# Adapter.net
KiCad netlist of a schematic drawn in EAGLE
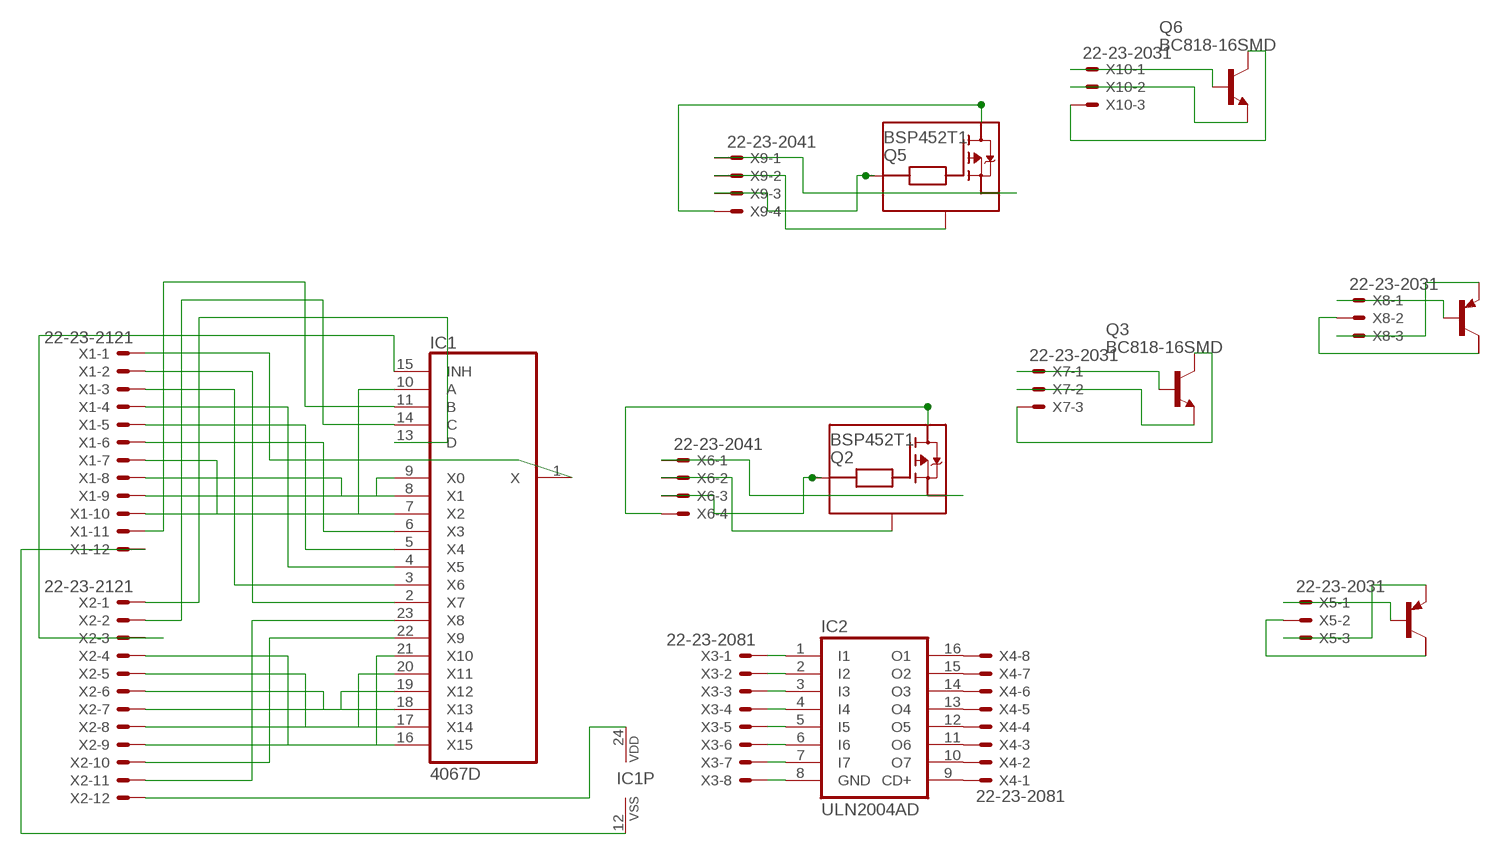
[diagram p0: schematic, sheet 1]
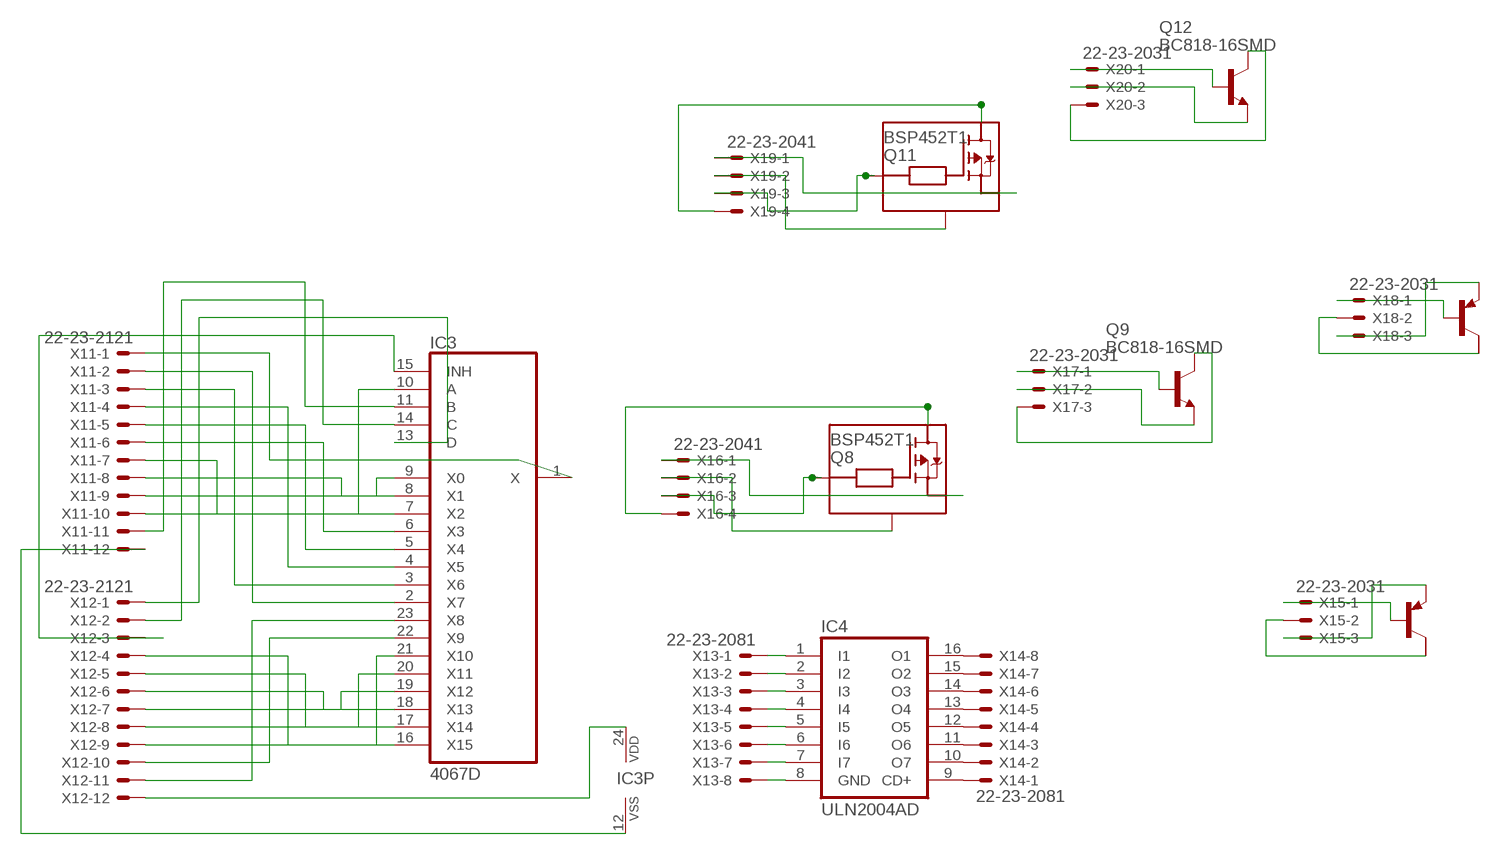
[diagram p1: schematic, sheet 2]
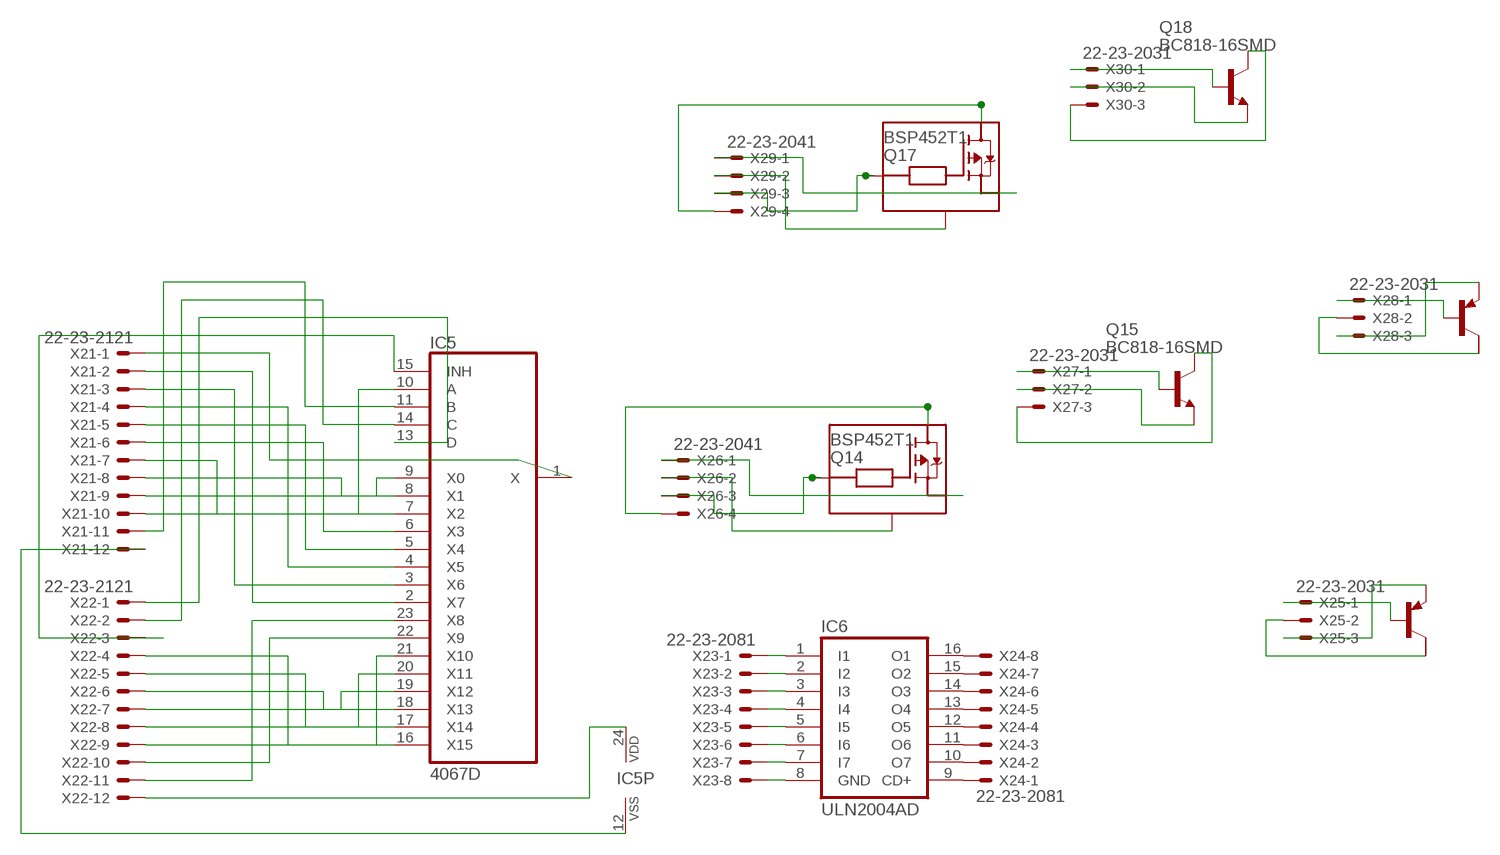
[diagram p2: schematic, sheet 3]
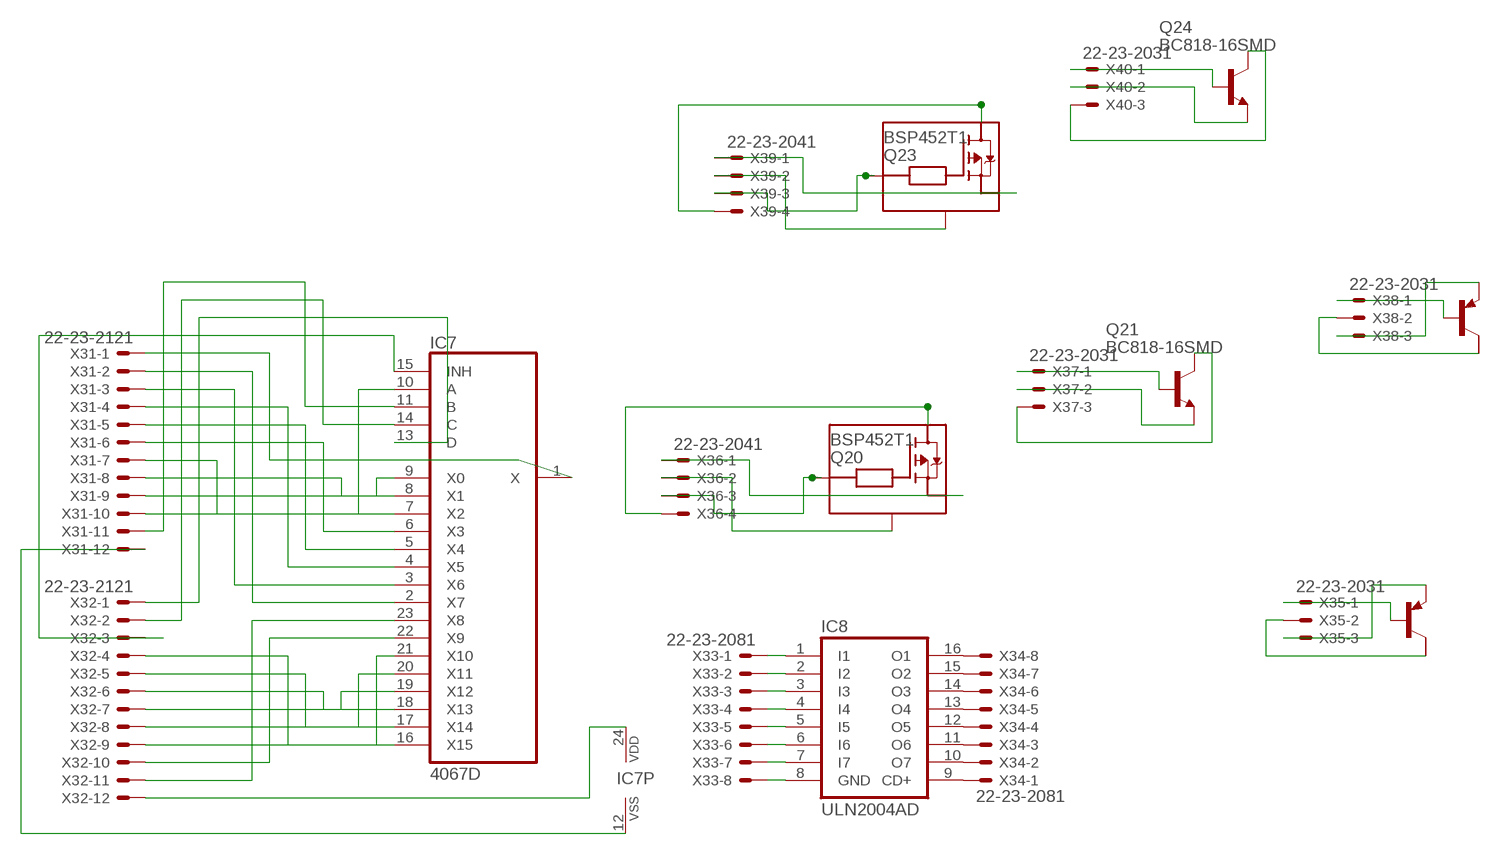
[diagram p3: schematic, sheet 4]
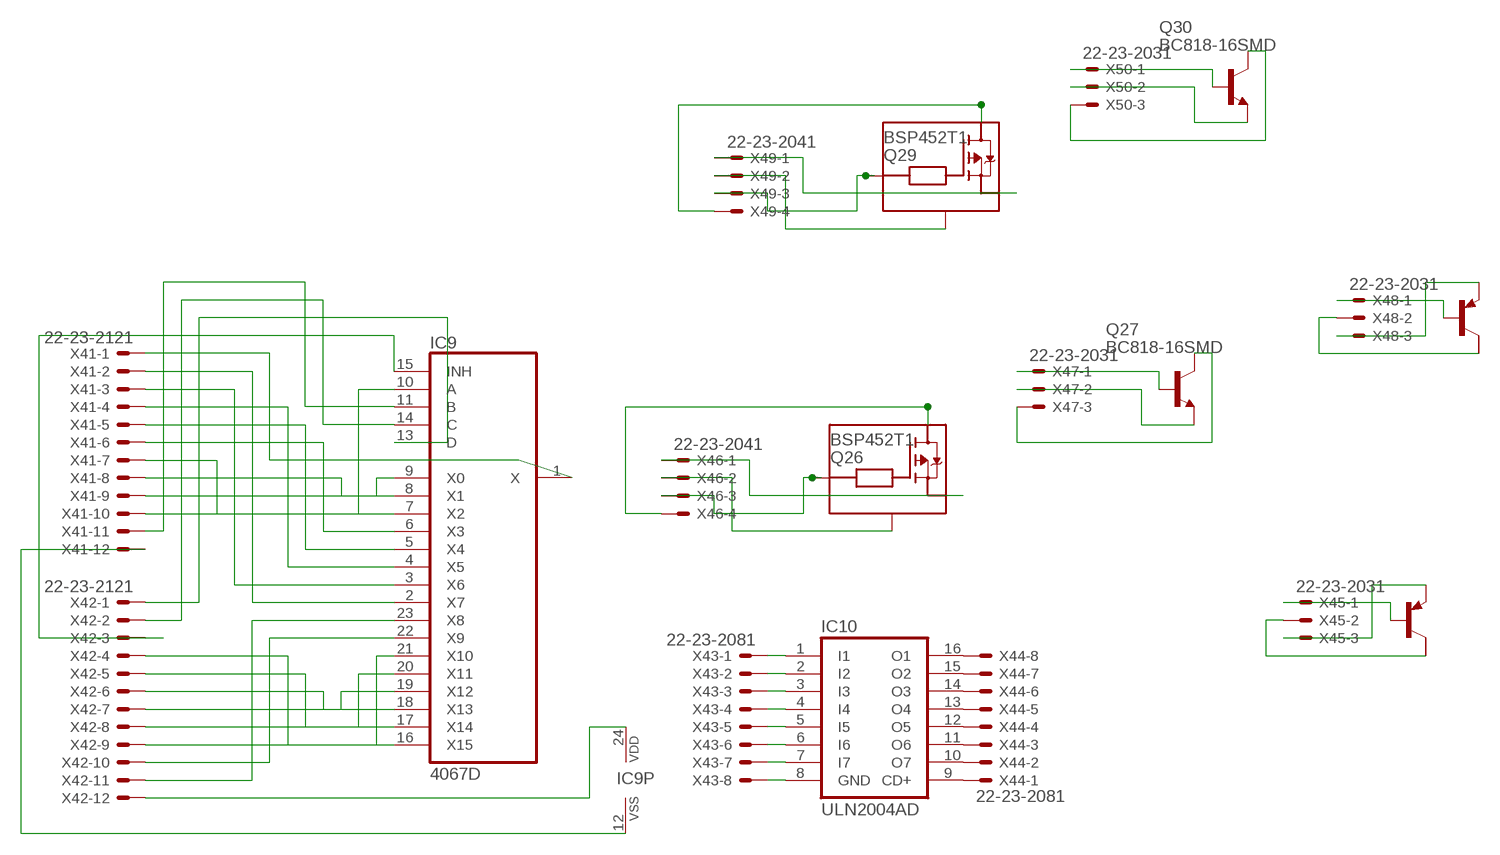
[diagram p4: schematic, sheet 5]
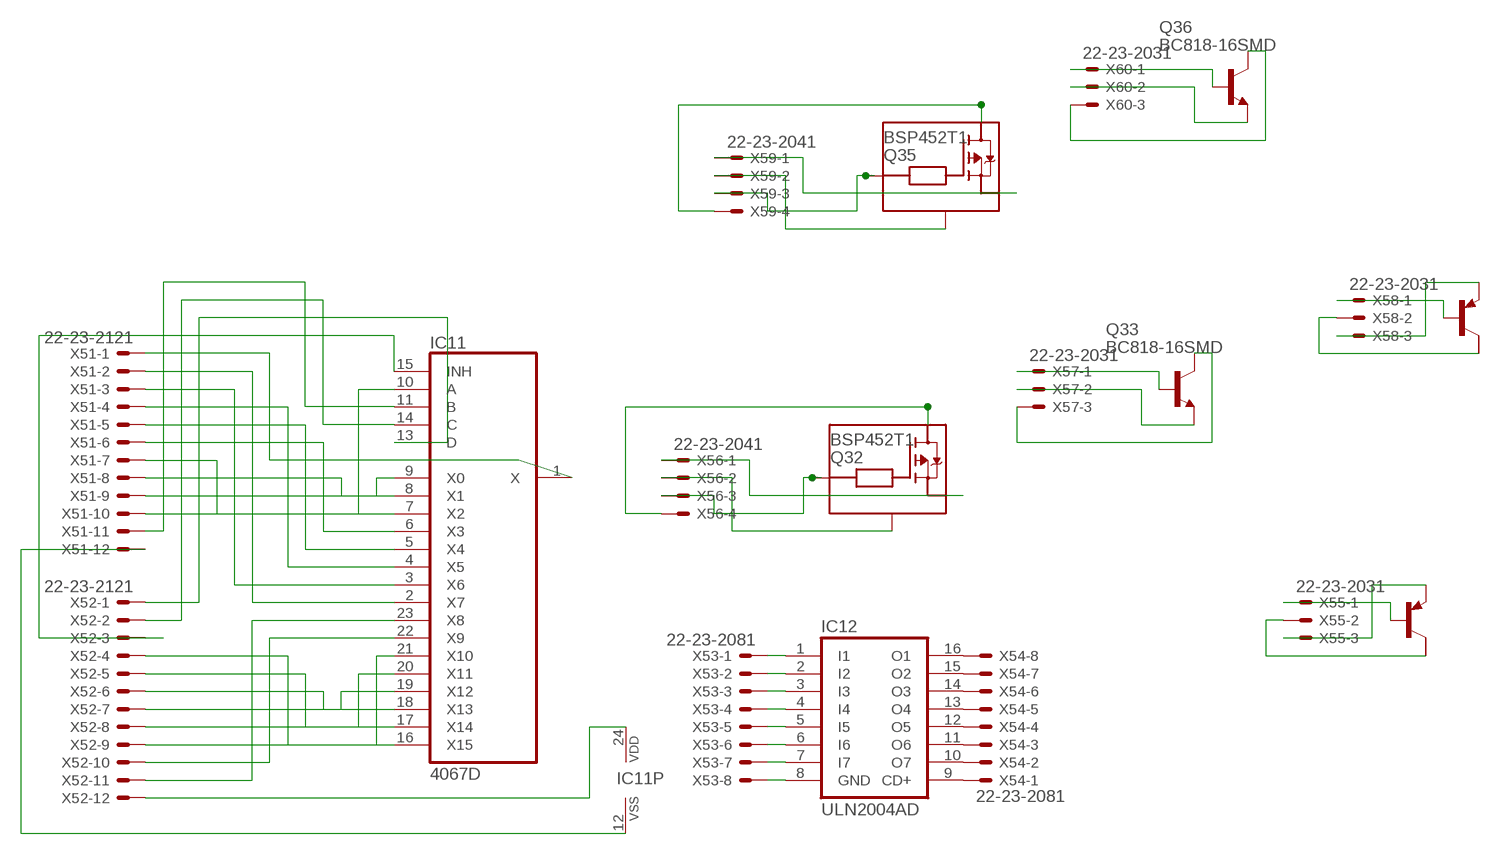
[diagram p5: schematic, sheet 6]
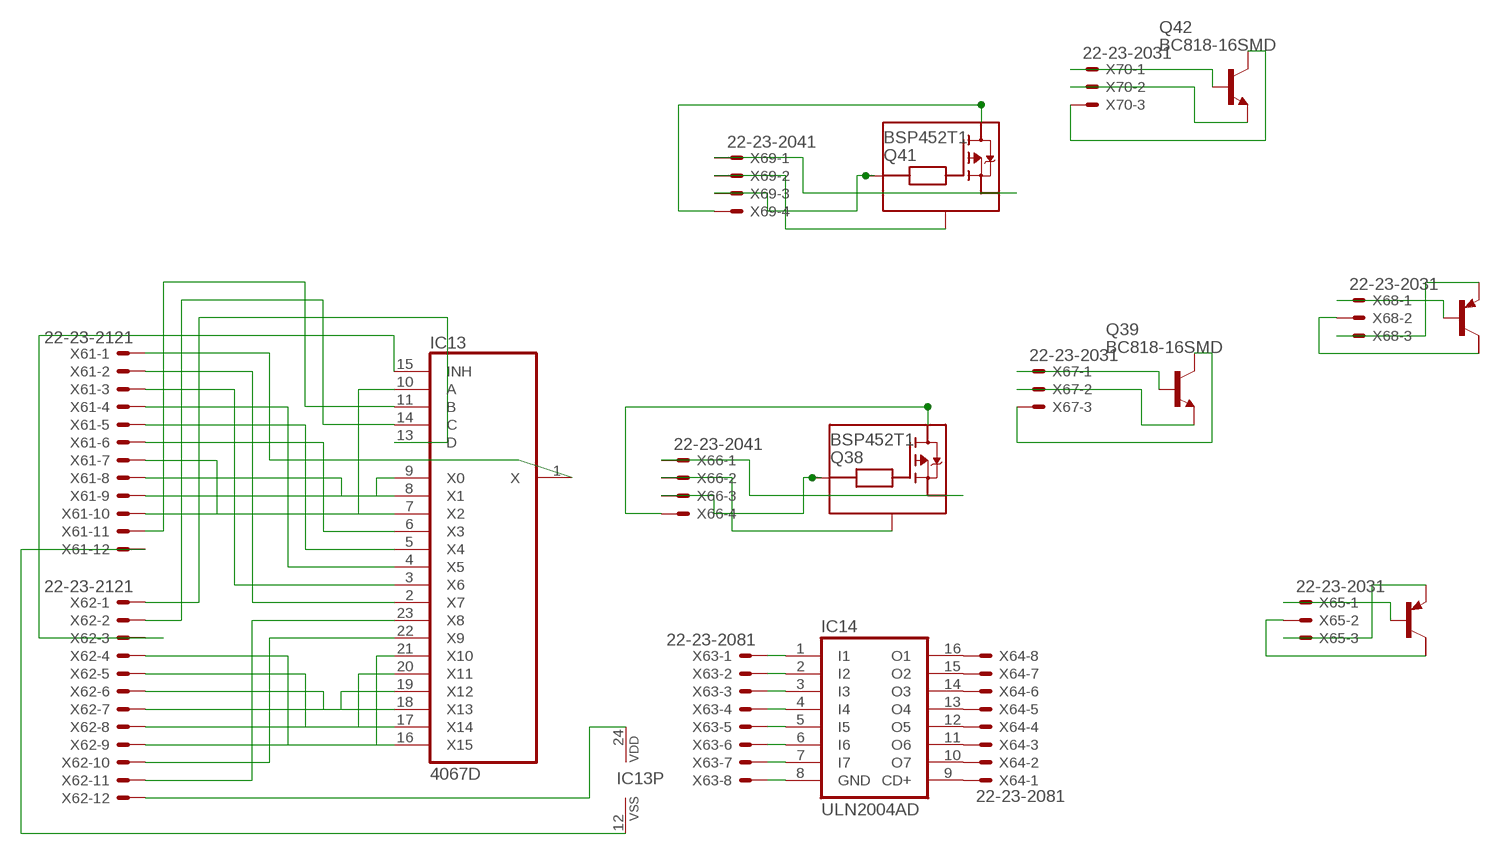
[diagram p6: schematic, sheet 7]
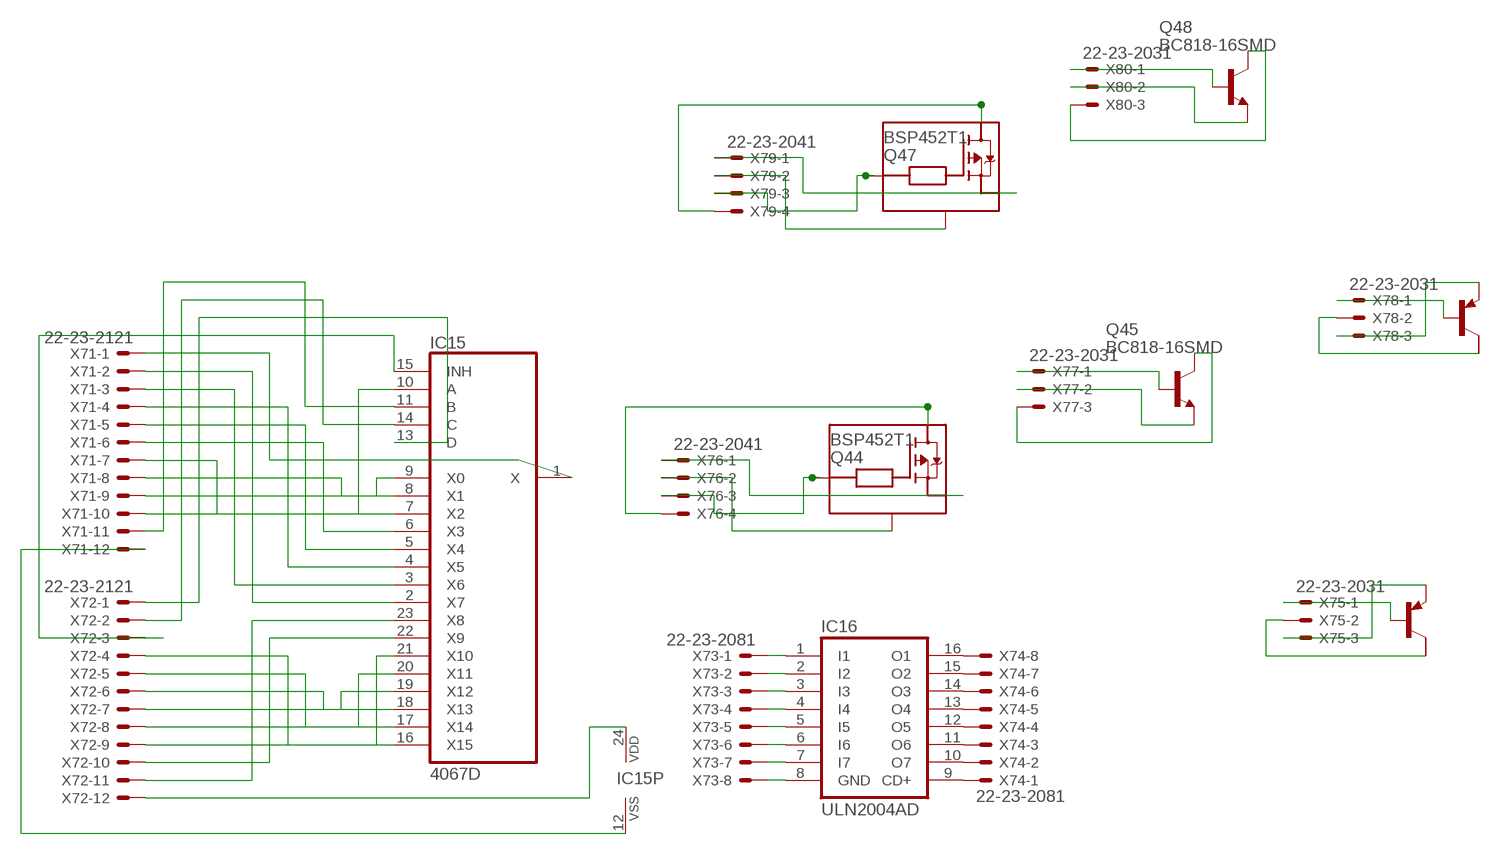
[diagram p7: schematic, sheet 8]

(export (version "E")
  (design (tool "Eeschema 10.0.6"))
  (components
    (comp (ref "IC11")
      (value "4067D")
      (footprint "eagle-import:SO24W")
      (libsource (lib "eagle-import") (part "4067D"))
    )
    (comp (ref "IC12")
      (value "ULN2004AD")
      (footprint "eagle-import:SO16")
      (libsource (lib "eagle-import") (part "ULN2004AD"))
    )
    (comp (ref "Q31")
      (value "BCP53T1")
      (footprint "eagle-import:SOT223")
      (libsource (lib "eagle-import") (part "BCP53T1"))
    )
    (comp (ref "Q32")
      (value "BSP452T1")
      (footprint "eagle-import:SOT223")
      (libsource (lib "eagle-import") (part "BSP452T1"))
    )
    (comp (ref "Q33")
      (value "BC818-16SMD")
      (footprint "eagle-import:SOT23-BEC")
      (libsource (lib "eagle-import") (part "BC818SMD-16"))
    )
    (comp (ref "Q34")
      (value "BCP53T1")
      (footprint "eagle-import:SOT223")
      (libsource (lib "eagle-import") (part "BCP53T1"))
    )
    (comp (ref "Q35")
      (value "BSP452T1")
      (footprint "eagle-import:SOT223")
      (libsource (lib "eagle-import") (part "BSP452T1"))
    )
    (comp (ref "Q36")
      (value "BC818-16SMD")
      (footprint "eagle-import:SOT23-BEC")
      (libsource (lib "eagle-import") (part "BC818SMD-16"))
    )
    (comp (ref "X51")
      (value "22-23-2121")
      (footprint "eagle-import:22-23-2121")
      (fields (field (name "MF") "MOLEX"))
      (libsource (lib "eagle-import") (part "22-23-2121"))
    )
    (comp (ref "X52")
      (value "22-23-2121")
      (footprint "eagle-import:22-23-2121")
      (fields (field (name "MF") "MOLEX"))
      (libsource (lib "eagle-import") (part "22-23-2121"))
    )
    (comp (ref "X53")
      (value "22-23-2081")
      (footprint "eagle-import:22-23-2081")
      (fields (field (name "MF") "MOLEX"))
      (libsource (lib "eagle-import") (part "22-23-2081"))
    )
    (comp (ref "X54")
      (value "22-23-2081")
      (footprint "eagle-import:22-23-2081")
      (fields (field (name "MF") "MOLEX"))
      (libsource (lib "eagle-import") (part "22-23-2081"))
    )
    (comp (ref "X55")
      (value "22-23-2031")
      (footprint "eagle-import:22-23-2031")
      (fields (field (name "MF") "MOLEX"))
      (libsource (lib "eagle-import") (part "22-23-2031"))
    )
    (comp (ref "X56")
      (value "22-23-2041")
      (footprint "eagle-import:22-23-2041")
      (fields (field (name "MF") "MOLEX"))
      (libsource (lib "eagle-import") (part "22-23-2041"))
    )
    (comp (ref "X57")
      (value "22-23-2031")
      (footprint "eagle-import:22-23-2031")
      (fields (field (name "MF") "MOLEX"))
      (libsource (lib "eagle-import") (part "22-23-2031"))
    )
    (comp (ref "X58")
      (value "22-23-2031")
      (footprint "eagle-import:22-23-2031")
      (fields (field (name "MF") "MOLEX"))
      (libsource (lib "eagle-import") (part "22-23-2031"))
    )
    (comp (ref "X59")
      (value "22-23-2041")
      (footprint "eagle-import:22-23-2041")
      (fields (field (name "MF") "MOLEX"))
      (libsource (lib "eagle-import") (part "22-23-2041"))
    )
    (comp (ref "X60")
      (value "22-23-2031")
      (footprint "eagle-import:22-23-2031")
      (fields (field (name "MF") "MOLEX"))
      (libsource (lib "eagle-import") (part "22-23-2031"))
    )
    (comp (ref "IC3")
      (value "4067D")
      (footprint "eagle-import:SO24W")
      (libsource (lib "eagle-import") (part "4067D"))
    )
    (comp (ref "IC4")
      (value "ULN2004AD")
      (footprint "eagle-import:SO16")
      (libsource (lib "eagle-import") (part "ULN2004AD"))
    )
    (comp (ref "Q7")
      (value "BCP53T1")
      (footprint "eagle-import:SOT223")
      (libsource (lib "eagle-import") (part "BCP53T1"))
    )
    (comp (ref "Q8")
      (value "BSP452T1")
      (footprint "eagle-import:SOT223")
      (libsource (lib "eagle-import") (part "BSP452T1"))
    )
    (comp (ref "Q9")
      (value "BC818-16SMD")
      (footprint "eagle-import:SOT23-BEC")
      (libsource (lib "eagle-import") (part "BC818SMD-16"))
    )
    (comp (ref "Q10")
      (value "BCP53T1")
      (footprint "eagle-import:SOT223")
      (libsource (lib "eagle-import") (part "BCP53T1"))
    )
    (comp (ref "Q11")
      (value "BSP452T1")
      (footprint "eagle-import:SOT223")
      (libsource (lib "eagle-import") (part "BSP452T1"))
    )
    (comp (ref "Q12")
      (value "BC818-16SMD")
      (footprint "eagle-import:SOT23-BEC")
      (libsource (lib "eagle-import") (part "BC818SMD-16"))
    )
    (comp (ref "X11")
      (value "22-23-2121")
      (footprint "eagle-import:22-23-2121")
      (fields (field (name "MF") "MOLEX"))
      (libsource (lib "eagle-import") (part "22-23-2121"))
    )
    (comp (ref "X12")
      (value "22-23-2121")
      (footprint "eagle-import:22-23-2121")
      (fields (field (name "MF") "MOLEX"))
      (libsource (lib "eagle-import") (part "22-23-2121"))
    )
    (comp (ref "X13")
      (value "22-23-2081")
      (footprint "eagle-import:22-23-2081")
      (fields (field (name "MF") "MOLEX"))
      (libsource (lib "eagle-import") (part "22-23-2081"))
    )
    (comp (ref "X14")
      (value "22-23-2081")
      (footprint "eagle-import:22-23-2081")
      (fields (field (name "MF") "MOLEX"))
      (libsource (lib "eagle-import") (part "22-23-2081"))
    )
    (comp (ref "X15")
      (value "22-23-2031")
      (footprint "eagle-import:22-23-2031")
      (fields (field (name "MF") "MOLEX"))
      (libsource (lib "eagle-import") (part "22-23-2031"))
    )
    (comp (ref "X16")
      (value "22-23-2041")
      (footprint "eagle-import:22-23-2041")
      (fields (field (name "MF") "MOLEX"))
      (libsource (lib "eagle-import") (part "22-23-2041"))
    )
    (comp (ref "X17")
      (value "22-23-2031")
      (footprint "eagle-import:22-23-2031")
      (fields (field (name "MF") "MOLEX"))
      (libsource (lib "eagle-import") (part "22-23-2031"))
    )
    (comp (ref "X18")
      (value "22-23-2031")
      (footprint "eagle-import:22-23-2031")
      (fields (field (name "MF") "MOLEX"))
      (libsource (lib "eagle-import") (part "22-23-2031"))
    )
    (comp (ref "X19")
      (value "22-23-2041")
      (footprint "eagle-import:22-23-2041")
      (fields (field (name "MF") "MOLEX"))
      (libsource (lib "eagle-import") (part "22-23-2041"))
    )
    (comp (ref "X20")
      (value "22-23-2031")
      (footprint "eagle-import:22-23-2031")
      (fields (field (name "MF") "MOLEX"))
      (libsource (lib "eagle-import") (part "22-23-2031"))
    )
    (comp (ref "IC15")
      (value "4067D")
      (footprint "eagle-import:SO24W")
      (libsource (lib "eagle-import") (part "4067D"))
    )
    (comp (ref "IC16")
      (value "ULN2004AD")
      (footprint "eagle-import:SO16")
      (libsource (lib "eagle-import") (part "ULN2004AD"))
    )
    (comp (ref "Q43")
      (value "BCP53T1")
      (footprint "eagle-import:SOT223")
      (libsource (lib "eagle-import") (part "BCP53T1"))
    )
    (comp (ref "Q44")
      (value "BSP452T1")
      (footprint "eagle-import:SOT223")
      (libsource (lib "eagle-import") (part "BSP452T1"))
    )
    (comp (ref "Q45")
      (value "BC818-16SMD")
      (footprint "eagle-import:SOT23-BEC")
      (libsource (lib "eagle-import") (part "BC818SMD-16"))
    )
    (comp (ref "Q46")
      (value "BCP53T1")
      (footprint "eagle-import:SOT223")
      (libsource (lib "eagle-import") (part "BCP53T1"))
    )
    (comp (ref "Q47")
      (value "BSP452T1")
      (footprint "eagle-import:SOT223")
      (libsource (lib "eagle-import") (part "BSP452T1"))
    )
    (comp (ref "Q48")
      (value "BC818-16SMD")
      (footprint "eagle-import:SOT23-BEC")
      (libsource (lib "eagle-import") (part "BC818SMD-16"))
    )
    (comp (ref "X71")
      (value "22-23-2121")
      (footprint "eagle-import:22-23-2121")
      (fields (field (name "MF") "MOLEX"))
      (libsource (lib "eagle-import") (part "22-23-2121"))
    )
    (comp (ref "X72")
      (value "22-23-2121")
      (footprint "eagle-import:22-23-2121")
      (fields (field (name "MF") "MOLEX"))
      (libsource (lib "eagle-import") (part "22-23-2121"))
    )
    (comp (ref "X73")
      (value "22-23-2081")
      (footprint "eagle-import:22-23-2081")
      (fields (field (name "MF") "MOLEX"))
      (libsource (lib "eagle-import") (part "22-23-2081"))
    )
    (comp (ref "X74")
      (value "22-23-2081")
      (footprint "eagle-import:22-23-2081")
      (fields (field (name "MF") "MOLEX"))
      (libsource (lib "eagle-import") (part "22-23-2081"))
    )
    (comp (ref "X75")
      (value "22-23-2031")
      (footprint "eagle-import:22-23-2031")
      (fields (field (name "MF") "MOLEX"))
      (libsource (lib "eagle-import") (part "22-23-2031"))
    )
    (comp (ref "X76")
      (value "22-23-2041")
      (footprint "eagle-import:22-23-2041")
      (fields (field (name "MF") "MOLEX"))
      (libsource (lib "eagle-import") (part "22-23-2041"))
    )
    (comp (ref "X77")
      (value "22-23-2031")
      (footprint "eagle-import:22-23-2031")
      (fields (field (name "MF") "MOLEX"))
      (libsource (lib "eagle-import") (part "22-23-2031"))
    )
    (comp (ref "X78")
      (value "22-23-2031")
      (footprint "eagle-import:22-23-2031")
      (fields (field (name "MF") "MOLEX"))
      (libsource (lib "eagle-import") (part "22-23-2031"))
    )
    (comp (ref "X79")
      (value "22-23-2041")
      (footprint "eagle-import:22-23-2041")
      (fields (field (name "MF") "MOLEX"))
      (libsource (lib "eagle-import") (part "22-23-2041"))
    )
    (comp (ref "X80")
      (value "22-23-2031")
      (footprint "eagle-import:22-23-2031")
      (fields (field (name "MF") "MOLEX"))
      (libsource (lib "eagle-import") (part "22-23-2031"))
    )
    (comp (ref "IC13")
      (value "4067D")
      (footprint "eagle-import:SO24W")
      (libsource (lib "eagle-import") (part "4067D"))
    )
    (comp (ref "IC14")
      (value "ULN2004AD")
      (footprint "eagle-import:SO16")
      (libsource (lib "eagle-import") (part "ULN2004AD"))
    )
    (comp (ref "Q37")
      (value "BCP53T1")
      (footprint "eagle-import:SOT223")
      (libsource (lib "eagle-import") (part "BCP53T1"))
    )
    (comp (ref "Q38")
      (value "BSP452T1")
      (footprint "eagle-import:SOT223")
      (libsource (lib "eagle-import") (part "BSP452T1"))
    )
    (comp (ref "Q39")
      (value "BC818-16SMD")
      (footprint "eagle-import:SOT23-BEC")
      (libsource (lib "eagle-import") (part "BC818SMD-16"))
    )
    (comp (ref "Q40")
      (value "BCP53T1")
      (footprint "eagle-import:SOT223")
      (libsource (lib "eagle-import") (part "BCP53T1"))
    )
    (comp (ref "Q41")
      (value "BSP452T1")
      (footprint "eagle-import:SOT223")
      (libsource (lib "eagle-import") (part "BSP452T1"))
    )
    (comp (ref "Q42")
      (value "BC818-16SMD")
      (footprint "eagle-import:SOT23-BEC")
      (libsource (lib "eagle-import") (part "BC818SMD-16"))
    )
    (comp (ref "X61")
      (value "22-23-2121")
      (footprint "eagle-import:22-23-2121")
      (fields (field (name "MF") "MOLEX"))
      (libsource (lib "eagle-import") (part "22-23-2121"))
    )
    (comp (ref "X62")
      (value "22-23-2121")
      (footprint "eagle-import:22-23-2121")
      (fields (field (name "MF") "MOLEX"))
      (libsource (lib "eagle-import") (part "22-23-2121"))
    )
    (comp (ref "X63")
      (value "22-23-2081")
      (footprint "eagle-import:22-23-2081")
      (fields (field (name "MF") "MOLEX"))
      (libsource (lib "eagle-import") (part "22-23-2081"))
    )
    (comp (ref "X64")
      (value "22-23-2081")
      (footprint "eagle-import:22-23-2081")
      (fields (field (name "MF") "MOLEX"))
      (libsource (lib "eagle-import") (part "22-23-2081"))
    )
    (comp (ref "X65")
      (value "22-23-2031")
      (footprint "eagle-import:22-23-2031")
      (fields (field (name "MF") "MOLEX"))
      (libsource (lib "eagle-import") (part "22-23-2031"))
    )
    (comp (ref "X66")
      (value "22-23-2041")
      (footprint "eagle-import:22-23-2041")
      (fields (field (name "MF") "MOLEX"))
      (libsource (lib "eagle-import") (part "22-23-2041"))
    )
    (comp (ref "X67")
      (value "22-23-2031")
      (footprint "eagle-import:22-23-2031")
      (fields (field (name "MF") "MOLEX"))
      (libsource (lib "eagle-import") (part "22-23-2031"))
    )
    (comp (ref "X68")
      (value "22-23-2031")
      (footprint "eagle-import:22-23-2031")
      (fields (field (name "MF") "MOLEX"))
      (libsource (lib "eagle-import") (part "22-23-2031"))
    )
    (comp (ref "X69")
      (value "22-23-2041")
      (footprint "eagle-import:22-23-2041")
      (fields (field (name "MF") "MOLEX"))
      (libsource (lib "eagle-import") (part "22-23-2041"))
    )
    (comp (ref "X70")
      (value "22-23-2031")
      (footprint "eagle-import:22-23-2031")
      (fields (field (name "MF") "MOLEX"))
      (libsource (lib "eagle-import") (part "22-23-2031"))
    )
    (comp (ref "IC1")
      (value "4067D")
      (footprint "eagle-import:SO24W")
      (libsource (lib "eagle-import") (part "4067D"))
    )
    (comp (ref "IC2")
      (value "ULN2004AD")
      (footprint "eagle-import:SO16")
      (libsource (lib "eagle-import") (part "ULN2004AD"))
    )
    (comp (ref "Q1")
      (value "BCP53T1")
      (footprint "eagle-import:SOT223")
      (libsource (lib "eagle-import") (part "BCP53T1"))
    )
    (comp (ref "Q2")
      (value "BSP452T1")
      (footprint "eagle-import:SOT223")
      (libsource (lib "eagle-import") (part "BSP452T1"))
    )
    (comp (ref "Q3")
      (value "BC818-16SMD")
      (footprint "eagle-import:SOT23-BEC")
      (libsource (lib "eagle-import") (part "BC818SMD-16"))
    )
    (comp (ref "Q4")
      (value "BCP53T1")
      (footprint "eagle-import:SOT223")
      (libsource (lib "eagle-import") (part "BCP53T1"))
    )
    (comp (ref "Q5")
      (value "BSP452T1")
      (footprint "eagle-import:SOT223")
      (libsource (lib "eagle-import") (part "BSP452T1"))
    )
    (comp (ref "Q6")
      (value "BC818-16SMD")
      (footprint "eagle-import:SOT23-BEC")
      (libsource (lib "eagle-import") (part "BC818SMD-16"))
    )
    (comp (ref "X1")
      (value "22-23-2121")
      (footprint "eagle-import:22-23-2121")
      (fields (field (name "MF") "MOLEX"))
      (libsource (lib "eagle-import") (part "22-23-2121"))
    )
    (comp (ref "X2")
      (value "22-23-2121")
      (footprint "eagle-import:22-23-2121")
      (fields (field (name "MF") "MOLEX"))
      (libsource (lib "eagle-import") (part "22-23-2121"))
    )
    (comp (ref "X3")
      (value "22-23-2081")
      (footprint "eagle-import:22-23-2081")
      (fields (field (name "MF") "MOLEX"))
      (libsource (lib "eagle-import") (part "22-23-2081"))
    )
    (comp (ref "X4")
      (value "22-23-2081")
      (footprint "eagle-import:22-23-2081")
      (fields (field (name "MF") "MOLEX"))
      (libsource (lib "eagle-import") (part "22-23-2081"))
    )
    (comp (ref "X5")
      (value "22-23-2031")
      (footprint "eagle-import:22-23-2031")
      (fields (field (name "MF") "MOLEX"))
      (libsource (lib "eagle-import") (part "22-23-2031"))
    )
    (comp (ref "X6")
      (value "22-23-2041")
      (footprint "eagle-import:22-23-2041")
      (fields (field (name "MF") "MOLEX"))
      (libsource (lib "eagle-import") (part "22-23-2041"))
    )
    (comp (ref "X7")
      (value "22-23-2031")
      (footprint "eagle-import:22-23-2031")
      (fields (field (name "MF") "MOLEX"))
      (libsource (lib "eagle-import") (part "22-23-2031"))
    )
    (comp (ref "X8")
      (value "22-23-2031")
      (footprint "eagle-import:22-23-2031")
      (fields (field (name "MF") "MOLEX"))
      (libsource (lib "eagle-import") (part "22-23-2031"))
    )
    (comp (ref "X9")
      (value "22-23-2041")
      (footprint "eagle-import:22-23-2041")
      (fields (field (name "MF") "MOLEX"))
      (libsource (lib "eagle-import") (part "22-23-2041"))
    )
    (comp (ref "X10")
      (value "22-23-2031")
      (footprint "eagle-import:22-23-2031")
      (fields (field (name "MF") "MOLEX"))
      (libsource (lib "eagle-import") (part "22-23-2031"))
    )
    (comp (ref "IC5")
      (value "4067D")
      (footprint "eagle-import:SO24W")
      (libsource (lib "eagle-import") (part "4067D"))
    )
    (comp (ref "IC6")
      (value "ULN2004AD")
      (footprint "eagle-import:SO16")
      (libsource (lib "eagle-import") (part "ULN2004AD"))
    )
    (comp (ref "Q13")
      (value "BCP53T1")
      (footprint "eagle-import:SOT223")
      (libsource (lib "eagle-import") (part "BCP53T1"))
    )
    (comp (ref "Q14")
      (value "BSP452T1")
      (footprint "eagle-import:SOT223")
      (libsource (lib "eagle-import") (part "BSP452T1"))
    )
    (comp (ref "Q15")
      (value "BC818-16SMD")
      (footprint "eagle-import:SOT23-BEC")
      (libsource (lib "eagle-import") (part "BC818SMD-16"))
    )
    (comp (ref "Q16")
      (value "BCP53T1")
      (footprint "eagle-import:SOT223")
      (libsource (lib "eagle-import") (part "BCP53T1"))
    )
    (comp (ref "Q17")
      (value "BSP452T1")
      (footprint "eagle-import:SOT223")
      (libsource (lib "eagle-import") (part "BSP452T1"))
    )
    (comp (ref "Q18")
      (value "BC818-16SMD")
      (footprint "eagle-import:SOT23-BEC")
      (libsource (lib "eagle-import") (part "BC818SMD-16"))
    )
    (comp (ref "X21")
      (value "22-23-2121")
      (footprint "eagle-import:22-23-2121")
      (fields (field (name "MF") "MOLEX"))
      (libsource (lib "eagle-import") (part "22-23-2121"))
    )
    (comp (ref "X22")
      (value "22-23-2121")
      (footprint "eagle-import:22-23-2121")
      (fields (field (name "MF") "MOLEX"))
      (libsource (lib "eagle-import") (part "22-23-2121"))
    )
    (comp (ref "X23")
      (value "22-23-2081")
      (footprint "eagle-import:22-23-2081")
      (fields (field (name "MF") "MOLEX"))
      (libsource (lib "eagle-import") (part "22-23-2081"))
    )
    (comp (ref "X24")
      (value "22-23-2081")
      (footprint "eagle-import:22-23-2081")
      (fields (field (name "MF") "MOLEX"))
      (libsource (lib "eagle-import") (part "22-23-2081"))
    )
    (comp (ref "X25")
      (value "22-23-2031")
      (footprint "eagle-import:22-23-2031")
      (fields (field (name "MF") "MOLEX"))
      (libsource (lib "eagle-import") (part "22-23-2031"))
    )
    (comp (ref "X26")
      (value "22-23-2041")
      (footprint "eagle-import:22-23-2041")
      (fields (field (name "MF") "MOLEX"))
      (libsource (lib "eagle-import") (part "22-23-2041"))
    )
    (comp (ref "X27")
      (value "22-23-2031")
      (footprint "eagle-import:22-23-2031")
      (fields (field (name "MF") "MOLEX"))
      (libsource (lib "eagle-import") (part "22-23-2031"))
    )
    (comp (ref "X28")
      (value "22-23-2031")
      (footprint "eagle-import:22-23-2031")
      (fields (field (name "MF") "MOLEX"))
      (libsource (lib "eagle-import") (part "22-23-2031"))
    )
    (comp (ref "X29")
      (value "22-23-2041")
      (footprint "eagle-import:22-23-2041")
      (fields (field (name "MF") "MOLEX"))
      (libsource (lib "eagle-import") (part "22-23-2041"))
    )
    (comp (ref "X30")
      (value "22-23-2031")
      (footprint "eagle-import:22-23-2031")
      (fields (field (name "MF") "MOLEX"))
      (libsource (lib "eagle-import") (part "22-23-2031"))
    )
    (comp (ref "IC9")
      (value "4067D")
      (footprint "eagle-import:SO24W")
      (libsource (lib "eagle-import") (part "4067D"))
    )
    (comp (ref "IC10")
      (value "ULN2004AD")
      (footprint "eagle-import:SO16")
      (libsource (lib "eagle-import") (part "ULN2004AD"))
    )
    (comp (ref "Q25")
      (value "BCP53T1")
      (footprint "eagle-import:SOT223")
      (libsource (lib "eagle-import") (part "BCP53T1"))
    )
    (comp (ref "Q26")
      (value "BSP452T1")
      (footprint "eagle-import:SOT223")
      (libsource (lib "eagle-import") (part "BSP452T1"))
    )
    (comp (ref "Q27")
      (value "BC818-16SMD")
      (footprint "eagle-import:SOT23-BEC")
      (libsource (lib "eagle-import") (part "BC818SMD-16"))
    )
    (comp (ref "Q28")
      (value "BCP53T1")
      (footprint "eagle-import:SOT223")
      (libsource (lib "eagle-import") (part "BCP53T1"))
    )
    (comp (ref "Q29")
      (value "BSP452T1")
      (footprint "eagle-import:SOT223")
      (libsource (lib "eagle-import") (part "BSP452T1"))
    )
    (comp (ref "Q30")
      (value "BC818-16SMD")
      (footprint "eagle-import:SOT23-BEC")
      (libsource (lib "eagle-import") (part "BC818SMD-16"))
    )
    (comp (ref "X41")
      (value "22-23-2121")
      (footprint "eagle-import:22-23-2121")
      (fields (field (name "MF") "MOLEX"))
      (libsource (lib "eagle-import") (part "22-23-2121"))
    )
    (comp (ref "X42")
      (value "22-23-2121")
      (footprint "eagle-import:22-23-2121")
      (fields (field (name "MF") "MOLEX"))
      (libsource (lib "eagle-import") (part "22-23-2121"))
    )
    (comp (ref "X43")
      (value "22-23-2081")
      (footprint "eagle-import:22-23-2081")
      (fields (field (name "MF") "MOLEX"))
      (libsource (lib "eagle-import") (part "22-23-2081"))
    )
    (comp (ref "X44")
      (value "22-23-2081")
      (footprint "eagle-import:22-23-2081")
      (fields (field (name "MF") "MOLEX"))
      (libsource (lib "eagle-import") (part "22-23-2081"))
    )
    (comp (ref "X45")
      (value "22-23-2031")
      (footprint "eagle-import:22-23-2031")
      (fields (field (name "MF") "MOLEX"))
      (libsource (lib "eagle-import") (part "22-23-2031"))
    )
    (comp (ref "X46")
      (value "22-23-2041")
      (footprint "eagle-import:22-23-2041")
      (fields (field (name "MF") "MOLEX"))
      (libsource (lib "eagle-import") (part "22-23-2041"))
    )
    (comp (ref "X47")
      (value "22-23-2031")
      (footprint "eagle-import:22-23-2031")
      (fields (field (name "MF") "MOLEX"))
      (libsource (lib "eagle-import") (part "22-23-2031"))
    )
    (comp (ref "X48")
      (value "22-23-2031")
      (footprint "eagle-import:22-23-2031")
      (fields (field (name "MF") "MOLEX"))
      (libsource (lib "eagle-import") (part "22-23-2031"))
    )
    (comp (ref "X49")
      (value "22-23-2041")
      (footprint "eagle-import:22-23-2041")
      (fields (field (name "MF") "MOLEX"))
      (libsource (lib "eagle-import") (part "22-23-2041"))
    )
    (comp (ref "X50")
      (value "22-23-2031")
      (footprint "eagle-import:22-23-2031")
      (fields (field (name "MF") "MOLEX"))
      (libsource (lib "eagle-import") (part "22-23-2031"))
    )
    (comp (ref "IC7")
      (value "4067D")
      (footprint "eagle-import:SO24W")
      (libsource (lib "eagle-import") (part "4067D"))
    )
    (comp (ref "IC8")
      (value "ULN2004AD")
      (footprint "eagle-import:SO16")
      (libsource (lib "eagle-import") (part "ULN2004AD"))
    )
    (comp (ref "Q19")
      (value "BCP53T1")
      (footprint "eagle-import:SOT223")
      (libsource (lib "eagle-import") (part "BCP53T1"))
    )
    (comp (ref "Q20")
      (value "BSP452T1")
      (footprint "eagle-import:SOT223")
      (libsource (lib "eagle-import") (part "BSP452T1"))
    )
    (comp (ref "Q21")
      (value "BC818-16SMD")
      (footprint "eagle-import:SOT23-BEC")
      (libsource (lib "eagle-import") (part "BC818SMD-16"))
    )
    (comp (ref "Q22")
      (value "BCP53T1")
      (footprint "eagle-import:SOT223")
      (libsource (lib "eagle-import") (part "BCP53T1"))
    )
    (comp (ref "Q23")
      (value "BSP452T1")
      (footprint "eagle-import:SOT223")
      (libsource (lib "eagle-import") (part "BSP452T1"))
    )
    (comp (ref "Q24")
      (value "BC818-16SMD")
      (footprint "eagle-import:SOT23-BEC")
      (libsource (lib "eagle-import") (part "BC818SMD-16"))
    )
    (comp (ref "X31")
      (value "22-23-2121")
      (footprint "eagle-import:22-23-2121")
      (fields (field (name "MF") "MOLEX"))
      (libsource (lib "eagle-import") (part "22-23-2121"))
    )
    (comp (ref "X32")
      (value "22-23-2121")
      (footprint "eagle-import:22-23-2121")
      (fields (field (name "MF") "MOLEX"))
      (libsource (lib "eagle-import") (part "22-23-2121"))
    )
    (comp (ref "X33")
      (value "22-23-2081")
      (footprint "eagle-import:22-23-2081")
      (fields (field (name "MF") "MOLEX"))
      (libsource (lib "eagle-import") (part "22-23-2081"))
    )
    (comp (ref "X34")
      (value "22-23-2081")
      (footprint "eagle-import:22-23-2081")
      (fields (field (name "MF") "MOLEX"))
      (libsource (lib "eagle-import") (part "22-23-2081"))
    )
    (comp (ref "X35")
      (value "22-23-2031")
      (footprint "eagle-import:22-23-2031")
      (fields (field (name "MF") "MOLEX"))
      (libsource (lib "eagle-import") (part "22-23-2031"))
    )
    (comp (ref "X36")
      (value "22-23-2041")
      (footprint "eagle-import:22-23-2041")
      (fields (field (name "MF") "MOLEX"))
      (libsource (lib "eagle-import") (part "22-23-2041"))
    )
    (comp (ref "X37")
      (value "22-23-2031")
      (footprint "eagle-import:22-23-2031")
      (fields (field (name "MF") "MOLEX"))
      (libsource (lib "eagle-import") (part "22-23-2031"))
    )
    (comp (ref "X38")
      (value "22-23-2031")
      (footprint "eagle-import:22-23-2031")
      (fields (field (name "MF") "MOLEX"))
      (libsource (lib "eagle-import") (part "22-23-2031"))
    )
    (comp (ref "X39")
      (value "22-23-2041")
      (footprint "eagle-import:22-23-2041")
      (fields (field (name "MF") "MOLEX"))
      (libsource (lib "eagle-import") (part "22-23-2041"))
    )
    (comp (ref "X40")
      (value "22-23-2031")
      (footprint "eagle-import:22-23-2031")
      (fields (field (name "MF") "MOLEX"))
      (libsource (lib "eagle-import") (part "22-23-2031"))
    )
  )
  (nets
    (net (code "1") (name "Net-(IC1A-A)") (class "Default")
      (node (ref "IC1") (pin "10") (pinfunction "A_10") (pintype "input"))
      (node (ref "X1") (pin "10") (pinfunction "S_10") (pintype "passive"))
    )
    (net (code "2") (name "Net-(IC1A-B)") (class "Default")
      (node (ref "IC1") (pin "11") (pinfunction "B_11") (pintype "input"))
      (node (ref "X1") (pin "11") (pinfunction "S_11") (pintype "passive"))
    )
    (net (code "3") (name "Net-(IC1A-C)") (class "Default")
      (node (ref "IC1") (pin "14") (pinfunction "C_14") (pintype "input"))
      (node (ref "X2") (pin "2") (pinfunction "S_2") (pintype "passive"))
    )
    (net (code "4") (name "Net-(IC1A-D)") (class "Default")
      (node (ref "IC1") (pin "13") (pinfunction "D_13") (pintype "input"))
      (node (ref "X2") (pin "1") (pinfunction "S_1") (pintype "passive"))
    )
    (net (code "5") (name "Net-(IC1A-INH)") (class "Default")
      (node (ref "IC1") (pin "15") (pinfunction "INH_15") (pintype "input"))
      (node (ref "X2") (pin "3") (pinfunction "S_3") (pintype "passive"))
    )
    (net (code "6") (name "Net-(IC1A-X)") (class "Default")
      (node (ref "IC1") (pin "1") (pinfunction "X_1") (pintype "output"))
      (node (ref "X1") (pin "1") (pinfunction "S_1") (pintype "passive"))
    )
    (net (code "7") (name "Net-(IC1A-X0)") (class "Default")
      (node (ref "IC1") (pin "9") (pinfunction "X0_9") (pintype "input"))
      (node (ref "X1") (pin "9") (pinfunction "S_9") (pintype "passive"))
    )
    (net (code "8") (name "Net-(IC1A-X1)") (class "Default")
      (node (ref "IC1") (pin "8") (pinfunction "X1_8") (pintype "input"))
      (node (ref "X1") (pin "8") (pinfunction "S_8") (pintype "passive"))
    )
    (net (code "9") (name "Net-(IC1A-X2)") (class "Default")
      (node (ref "IC1") (pin "7") (pinfunction "X2_7") (pintype "input"))
      (node (ref "X1") (pin "7") (pinfunction "S_7") (pintype "passive"))
    )
    (net (code "10") (name "Net-(IC1A-X3)") (class "Default")
      (node (ref "IC1") (pin "6") (pinfunction "X3_6") (pintype "input"))
      (node (ref "X1") (pin "6") (pinfunction "S_6") (pintype "passive"))
    )
    (net (code "11") (name "Net-(IC1A-X4)") (class "Default")
      (node (ref "IC1") (pin "5") (pinfunction "X4_5") (pintype "input"))
      (node (ref "X1") (pin "5") (pinfunction "S_5") (pintype "passive"))
    )
    (net (code "12") (name "Net-(IC1A-X5)") (class "Default")
      (node (ref "IC1") (pin "4") (pinfunction "X5_4") (pintype "input"))
      (node (ref "X1") (pin "4") (pinfunction "S_4") (pintype "passive"))
    )
    (net (code "13") (name "Net-(IC1A-X6)") (class "Default")
      (node (ref "IC1") (pin "3") (pinfunction "X6_3") (pintype "input"))
      (node (ref "X1") (pin "3") (pinfunction "S_3") (pintype "passive"))
    )
    (net (code "14") (name "Net-(IC1A-X7)") (class "Default")
      (node (ref "IC1") (pin "2") (pinfunction "X7_2") (pintype "input"))
      (node (ref "X1") (pin "2") (pinfunction "S_2") (pintype "passive"))
    )
    (net (code "15") (name "Net-(IC1A-X8)") (class "Default")
      (node (ref "IC1") (pin "23") (pinfunction "X8_23") (pintype "input"))
      (node (ref "X2") (pin "11") (pinfunction "S_11") (pintype "passive"))
    )
    (net (code "16") (name "Net-(IC1A-X9)") (class "Default")
      (node (ref "IC1") (pin "22") (pinfunction "X9_22") (pintype "input"))
      (node (ref "X2") (pin "10") (pinfunction "S_10") (pintype "passive"))
    )
    (net (code "17") (name "Net-(IC1A-X10)") (class "Default")
      (node (ref "IC1") (pin "21") (pinfunction "X10_21") (pintype "input"))
      (node (ref "X2") (pin "9") (pinfunction "S_9") (pintype "passive"))
    )
    (net (code "18") (name "Net-(IC1A-X11)") (class "Default")
      (node (ref "IC1") (pin "20") (pinfunction "X11_20") (pintype "input"))
      (node (ref "X2") (pin "8") (pinfunction "S_8") (pintype "passive"))
    )
    (net (code "19") (name "Net-(IC1A-X12)") (class "Default")
      (node (ref "IC1") (pin "19") (pinfunction "X12_19") (pintype "input"))
      (node (ref "X2") (pin "7") (pinfunction "S_7") (pintype "passive"))
    )
    (net (code "20") (name "Net-(IC1A-X13)") (class "Default")
      (node (ref "IC1") (pin "18") (pinfunction "X13_18") (pintype "input"))
      (node (ref "X2") (pin "6") (pinfunction "S_6") (pintype "passive"))
    )
    (net (code "21") (name "Net-(IC1A-X14)") (class "Default")
      (node (ref "IC1") (pin "17") (pinfunction "X14_17") (pintype "input"))
      (node (ref "X2") (pin "5") (pinfunction "S_5") (pintype "passive"))
    )
    (net (code "22") (name "Net-(IC1A-X15)") (class "Default")
      (node (ref "IC1") (pin "16") (pinfunction "X15_16") (pintype "input"))
      (node (ref "X2") (pin "4") (pinfunction "S_4") (pintype "passive"))
    )
    (net (code "23") (name "Net-(IC1B-VDD)") (class "Default")
      (node (ref "IC1") (pin "24") (pinfunction "VDD_24") (pintype "power_in"))
      (node (ref "X2") (pin "12") (pinfunction "S_12") (pintype "passive"))
    )
    (net (code "24") (name "Net-(IC1B-VSS)") (class "Default")
      (node (ref "IC1") (pin "12") (pinfunction "VSS_12") (pintype "power_in"))
      (node (ref "X1") (pin "12") (pinfunction "S_12") (pintype "passive"))
    )
    (net (code "25") (name "Net-(IC2-CD+)") (class "Default")
      (node (ref "IC2") (pin "9") (pinfunction "CD+_9") (pintype "passive"))
      (node (ref "X4") (pin "1") (pinfunction "S_1") (pintype "passive"))
    )
    (net (code "26") (name "Net-(IC2-GND)") (class "Default")
      (node (ref "IC2") (pin "8") (pinfunction "GND_8") (pintype "power_in"))
      (node (ref "X3") (pin "8") (pinfunction "S_8") (pintype "passive"))
    )
    (net (code "27") (name "Net-(IC2-I1)") (class "Default")
      (node (ref "IC2") (pin "1") (pinfunction "I1_1") (pintype "input"))
      (node (ref "X3") (pin "1") (pinfunction "S_1") (pintype "passive"))
    )
    (net (code "28") (name "Net-(IC2-I2)") (class "Default")
      (node (ref "IC2") (pin "2") (pinfunction "I2_2") (pintype "input"))
      (node (ref "X3") (pin "2") (pinfunction "S_2") (pintype "passive"))
    )
    (net (code "29") (name "Net-(IC2-I3)") (class "Default")
      (node (ref "IC2") (pin "3") (pinfunction "I3_3") (pintype "input"))
      (node (ref "X3") (pin "3") (pinfunction "S_3") (pintype "passive"))
    )
    (net (code "30") (name "Net-(IC2-I4)") (class "Default")
      (node (ref "IC2") (pin "4") (pinfunction "I4_4") (pintype "input"))
      (node (ref "X3") (pin "4") (pinfunction "S_4") (pintype "passive"))
    )
    (net (code "31") (name "Net-(IC2-I5)") (class "Default")
      (node (ref "IC2") (pin "5") (pinfunction "I5_5") (pintype "input"))
      (node (ref "X3") (pin "5") (pinfunction "S_5") (pintype "passive"))
    )
    (net (code "32") (name "Net-(IC2-I6)") (class "Default")
      (node (ref "IC2") (pin "6") (pinfunction "I6_6") (pintype "input"))
      (node (ref "X3") (pin "6") (pinfunction "S_6") (pintype "passive"))
    )
    (net (code "33") (name "Net-(IC2-I7)") (class "Default")
      (node (ref "IC2") (pin "7") (pinfunction "I7_7") (pintype "input"))
      (node (ref "X3") (pin "7") (pinfunction "S_7") (pintype "passive"))
    )
    (net (code "34") (name "Net-(IC2-O1)") (class "Default")
      (node (ref "IC2") (pin "16") (pinfunction "O1_16") (pintype "open_collector"))
      (node (ref "X4") (pin "8") (pinfunction "S_8") (pintype "passive"))
    )
    (net (code "35") (name "Net-(IC2-O2)") (class "Default")
      (node (ref "IC2") (pin "15") (pinfunction "O2_15") (pintype "open_collector"))
      (node (ref "X4") (pin "7") (pinfunction "S_7") (pintype "passive"))
    )
    (net (code "36") (name "Net-(IC2-O3)") (class "Default")
      (node (ref "IC2") (pin "14") (pinfunction "O3_14") (pintype "open_collector"))
      (node (ref "X4") (pin "6") (pinfunction "S_6") (pintype "passive"))
    )
    (net (code "37") (name "Net-(IC2-O4)") (class "Default")
      (node (ref "IC2") (pin "13") (pinfunction "O4_13") (pintype "open_collector"))
      (node (ref "X4") (pin "5") (pinfunction "S_5") (pintype "passive"))
    )
    (net (code "38") (name "Net-(IC2-O5)") (class "Default")
      (node (ref "IC2") (pin "12") (pinfunction "O5_12") (pintype "open_collector"))
      (node (ref "X4") (pin "4") (pinfunction "S_4") (pintype "passive"))
    )
    (net (code "39") (name "Net-(IC2-O6)") (class "Default")
      (node (ref "IC2") (pin "11") (pinfunction "O6_11") (pintype "open_collector"))
      (node (ref "X4") (pin "3") (pinfunction "S_3") (pintype "passive"))
    )
    (net (code "40") (name "Net-(IC2-O7)") (class "Default")
      (node (ref "IC2") (pin "10") (pinfunction "O7_10") (pintype "open_collector"))
      (node (ref "X4") (pin "2") (pinfunction "S_2") (pintype "passive"))
    )
    (net (code "41") (name "Net-(IC3A-A)") (class "Default")
      (node (ref "IC3") (pin "10") (pinfunction "A_10") (pintype "input"))
      (node (ref "X11") (pin "10") (pinfunction "S_10") (pintype "passive"))
    )
    (net (code "42") (name "Net-(IC3A-B)") (class "Default")
      (node (ref "IC3") (pin "11") (pinfunction "B_11") (pintype "input"))
      (node (ref "X11") (pin "11") (pinfunction "S_11") (pintype "passive"))
    )
    (net (code "43") (name "Net-(IC3A-C)") (class "Default")
      (node (ref "IC3") (pin "14") (pinfunction "C_14") (pintype "input"))
      (node (ref "X12") (pin "2") (pinfunction "S_2") (pintype "passive"))
    )
    (net (code "44") (name "Net-(IC3A-D)") (class "Default")
      (node (ref "IC3") (pin "13") (pinfunction "D_13") (pintype "input"))
      (node (ref "X12") (pin "1") (pinfunction "S_1") (pintype "passive"))
    )
    (net (code "45") (name "Net-(IC3A-INH)") (class "Default")
      (node (ref "IC3") (pin "15") (pinfunction "INH_15") (pintype "input"))
      (node (ref "X12") (pin "3") (pinfunction "S_3") (pintype "passive"))
    )
    (net (code "46") (name "Net-(IC3A-X)") (class "Default")
      (node (ref "IC3") (pin "1") (pinfunction "X_1") (pintype "output"))
      (node (ref "X11") (pin "1") (pinfunction "S_1") (pintype "passive"))
    )
    (net (code "47") (name "Net-(IC3A-X0)") (class "Default")
      (node (ref "IC3") (pin "9") (pinfunction "X0_9") (pintype "input"))
      (node (ref "X11") (pin "9") (pinfunction "S_9") (pintype "passive"))
    )
    (net (code "48") (name "Net-(IC3A-X1)") (class "Default")
      (node (ref "IC3") (pin "8") (pinfunction "X1_8") (pintype "input"))
      (node (ref "X11") (pin "8") (pinfunction "S_8") (pintype "passive"))
    )
    (net (code "49") (name "Net-(IC3A-X2)") (class "Default")
      (node (ref "IC3") (pin "7") (pinfunction "X2_7") (pintype "input"))
      (node (ref "X11") (pin "7") (pinfunction "S_7") (pintype "passive"))
    )
    (net (code "50") (name "Net-(IC3A-X3)") (class "Default")
      (node (ref "IC3") (pin "6") (pinfunction "X3_6") (pintype "input"))
      (node (ref "X11") (pin "6") (pinfunction "S_6") (pintype "passive"))
    )
    (net (code "51") (name "Net-(IC3A-X4)") (class "Default")
      (node (ref "IC3") (pin "5") (pinfunction "X4_5") (pintype "input"))
      (node (ref "X11") (pin "5") (pinfunction "S_5") (pintype "passive"))
    )
    (net (code "52") (name "Net-(IC3A-X5)") (class "Default")
      (node (ref "IC3") (pin "4") (pinfunction "X5_4") (pintype "input"))
      (node (ref "X11") (pin "4") (pinfunction "S_4") (pintype "passive"))
    )
    (net (code "53") (name "Net-(IC3A-X6)") (class "Default")
      (node (ref "IC3") (pin "3") (pinfunction "X6_3") (pintype "input"))
      (node (ref "X11") (pin "3") (pinfunction "S_3") (pintype "passive"))
    )
    (net (code "54") (name "Net-(IC3A-X7)") (class "Default")
      (node (ref "IC3") (pin "2") (pinfunction "X7_2") (pintype "input"))
      (node (ref "X11") (pin "2") (pinfunction "S_2") (pintype "passive"))
    )
    (net (code "55") (name "Net-(IC3A-X8)") (class "Default")
      (node (ref "IC3") (pin "23") (pinfunction "X8_23") (pintype "input"))
      (node (ref "X12") (pin "11") (pinfunction "S_11") (pintype "passive"))
    )
    (net (code "56") (name "Net-(IC3A-X9)") (class "Default")
      (node (ref "IC3") (pin "22") (pinfunction "X9_22") (pintype "input"))
      (node (ref "X12") (pin "10") (pinfunction "S_10") (pintype "passive"))
    )
    (net (code "57") (name "Net-(IC3A-X10)") (class "Default")
      (node (ref "IC3") (pin "21") (pinfunction "X10_21") (pintype "input"))
      (node (ref "X12") (pin "9") (pinfunction "S_9") (pintype "passive"))
    )
    (net (code "58") (name "Net-(IC3A-X11)") (class "Default")
      (node (ref "IC3") (pin "20") (pinfunction "X11_20") (pintype "input"))
      (node (ref "X12") (pin "8") (pinfunction "S_8") (pintype "passive"))
    )
    (net (code "59") (name "Net-(IC3A-X12)") (class "Default")
      (node (ref "IC3") (pin "19") (pinfunction "X12_19") (pintype "input"))
      (node (ref "X12") (pin "7") (pinfunction "S_7") (pintype "passive"))
    )
    (net (code "60") (name "Net-(IC3A-X13)") (class "Default")
      (node (ref "IC3") (pin "18") (pinfunction "X13_18") (pintype "input"))
      (node (ref "X12") (pin "6") (pinfunction "S_6") (pintype "passive"))
    )
    (net (code "61") (name "Net-(IC3A-X14)") (class "Default")
      (node (ref "IC3") (pin "17") (pinfunction "X14_17") (pintype "input"))
      (node (ref "X12") (pin "5") (pinfunction "S_5") (pintype "passive"))
    )
    (net (code "62") (name "Net-(IC3A-X15)") (class "Default")
      (node (ref "IC3") (pin "16") (pinfunction "X15_16") (pintype "input"))
      (node (ref "X12") (pin "4") (pinfunction "S_4") (pintype "passive"))
    )
    (net (code "63") (name "Net-(IC3B-VDD)") (class "Default")
      (node (ref "IC3") (pin "24") (pinfunction "VDD_24") (pintype "power_in"))
      (node (ref "X12") (pin "12") (pinfunction "S_12") (pintype "passive"))
    )
    (net (code "64") (name "Net-(IC3B-VSS)") (class "Default")
      (node (ref "IC3") (pin "12") (pinfunction "VSS_12") (pintype "power_in"))
      (node (ref "X11") (pin "12") (pinfunction "S_12") (pintype "passive"))
    )
    (net (code "65") (name "Net-(IC4-CD+)") (class "Default")
      (node (ref "IC4") (pin "9") (pinfunction "CD+_9") (pintype "passive"))
      (node (ref "X14") (pin "1") (pinfunction "S_1") (pintype "passive"))
    )
    (net (code "66") (name "Net-(IC4-GND)") (class "Default")
      (node (ref "IC4") (pin "8") (pinfunction "GND_8") (pintype "power_in"))
      (node (ref "X13") (pin "8") (pinfunction "S_8") (pintype "passive"))
    )
    (net (code "67") (name "Net-(IC4-I1)") (class "Default")
      (node (ref "IC4") (pin "1") (pinfunction "I1_1") (pintype "input"))
      (node (ref "X13") (pin "1") (pinfunction "S_1") (pintype "passive"))
    )
    (net (code "68") (name "Net-(IC4-I2)") (class "Default")
      (node (ref "IC4") (pin "2") (pinfunction "I2_2") (pintype "input"))
      (node (ref "X13") (pin "2") (pinfunction "S_2") (pintype "passive"))
    )
    (net (code "69") (name "Net-(IC4-I3)") (class "Default")
      (node (ref "IC4") (pin "3") (pinfunction "I3_3") (pintype "input"))
      (node (ref "X13") (pin "3") (pinfunction "S_3") (pintype "passive"))
    )
    (net (code "70") (name "Net-(IC4-I4)") (class "Default")
      (node (ref "IC4") (pin "4") (pinfunction "I4_4") (pintype "input"))
      (node (ref "X13") (pin "4") (pinfunction "S_4") (pintype "passive"))
    )
    (net (code "71") (name "Net-(IC4-I5)") (class "Default")
      (node (ref "IC4") (pin "5") (pinfunction "I5_5") (pintype "input"))
      (node (ref "X13") (pin "5") (pinfunction "S_5") (pintype "passive"))
    )
    (net (code "72") (name "Net-(IC4-I6)") (class "Default")
      (node (ref "IC4") (pin "6") (pinfunction "I6_6") (pintype "input"))
      (node (ref "X13") (pin "6") (pinfunction "S_6") (pintype "passive"))
    )
    (net (code "73") (name "Net-(IC4-I7)") (class "Default")
      (node (ref "IC4") (pin "7") (pinfunction "I7_7") (pintype "input"))
      (node (ref "X13") (pin "7") (pinfunction "S_7") (pintype "passive"))
    )
    (net (code "74") (name "Net-(IC4-O1)") (class "Default")
      (node (ref "IC4") (pin "16") (pinfunction "O1_16") (pintype "open_collector"))
      (node (ref "X14") (pin "8") (pinfunction "S_8") (pintype "passive"))
    )
    (net (code "75") (name "Net-(IC4-O2)") (class "Default")
      (node (ref "IC4") (pin "15") (pinfunction "O2_15") (pintype "open_collector"))
      (node (ref "X14") (pin "7") (pinfunction "S_7") (pintype "passive"))
    )
    (net (code "76") (name "Net-(IC4-O3)") (class "Default")
      (node (ref "IC4") (pin "14") (pinfunction "O3_14") (pintype "open_collector"))
      (node (ref "X14") (pin "6") (pinfunction "S_6") (pintype "passive"))
    )
    (net (code "77") (name "Net-(IC4-O4)") (class "Default")
      (node (ref "IC4") (pin "13") (pinfunction "O4_13") (pintype "open_collector"))
      (node (ref "X14") (pin "5") (pinfunction "S_5") (pintype "passive"))
    )
    (net (code "78") (name "Net-(IC4-O5)") (class "Default")
      (node (ref "IC4") (pin "12") (pinfunction "O5_12") (pintype "open_collector"))
      (node (ref "X14") (pin "4") (pinfunction "S_4") (pintype "passive"))
    )
    (net (code "79") (name "Net-(IC4-O6)") (class "Default")
      (node (ref "IC4") (pin "11") (pinfunction "O6_11") (pintype "open_collector"))
      (node (ref "X14") (pin "3") (pinfunction "S_3") (pintype "passive"))
    )
    (net (code "80") (name "Net-(IC4-O7)") (class "Default")
      (node (ref "IC4") (pin "10") (pinfunction "O7_10") (pintype "open_collector"))
      (node (ref "X14") (pin "2") (pinfunction "S_2") (pintype "passive"))
    )
    (net (code "81") (name "Net-(IC5A-A)") (class "Default")
      (node (ref "IC5") (pin "10") (pinfunction "A_10") (pintype "input"))
      (node (ref "X21") (pin "10") (pinfunction "S_10") (pintype "passive"))
    )
    (net (code "82") (name "Net-(IC5A-B)") (class "Default")
      (node (ref "IC5") (pin "11") (pinfunction "B_11") (pintype "input"))
      (node (ref "X21") (pin "11") (pinfunction "S_11") (pintype "passive"))
    )
    (net (code "83") (name "Net-(IC5A-C)") (class "Default")
      (node (ref "IC5") (pin "14") (pinfunction "C_14") (pintype "input"))
      (node (ref "X22") (pin "2") (pinfunction "S_2") (pintype "passive"))
    )
    (net (code "84") (name "Net-(IC5A-D)") (class "Default")
      (node (ref "IC5") (pin "13") (pinfunction "D_13") (pintype "input"))
      (node (ref "X22") (pin "1") (pinfunction "S_1") (pintype "passive"))
    )
    (net (code "85") (name "Net-(IC5A-INH)") (class "Default")
      (node (ref "IC5") (pin "15") (pinfunction "INH_15") (pintype "input"))
      (node (ref "X22") (pin "3") (pinfunction "S_3") (pintype "passive"))
    )
    (net (code "86") (name "Net-(IC5A-X)") (class "Default")
      (node (ref "IC5") (pin "1") (pinfunction "X_1") (pintype "output"))
      (node (ref "X21") (pin "1") (pinfunction "S_1") (pintype "passive"))
    )
    (net (code "87") (name "Net-(IC5A-X0)") (class "Default")
      (node (ref "IC5") (pin "9") (pinfunction "X0_9") (pintype "input"))
      (node (ref "X21") (pin "9") (pinfunction "S_9") (pintype "passive"))
    )
    (net (code "88") (name "Net-(IC5A-X1)") (class "Default")
      (node (ref "IC5") (pin "8") (pinfunction "X1_8") (pintype "input"))
      (node (ref "X21") (pin "8") (pinfunction "S_8") (pintype "passive"))
    )
    (net (code "89") (name "Net-(IC5A-X2)") (class "Default")
      (node (ref "IC5") (pin "7") (pinfunction "X2_7") (pintype "input"))
      (node (ref "X21") (pin "7") (pinfunction "S_7") (pintype "passive"))
    )
    (net (code "90") (name "Net-(IC5A-X3)") (class "Default")
      (node (ref "IC5") (pin "6") (pinfunction "X3_6") (pintype "input"))
      (node (ref "X21") (pin "6") (pinfunction "S_6") (pintype "passive"))
    )
    (net (code "91") (name "Net-(IC5A-X4)") (class "Default")
      (node (ref "IC5") (pin "5") (pinfunction "X4_5") (pintype "input"))
      (node (ref "X21") (pin "5") (pinfunction "S_5") (pintype "passive"))
    )
    (net (code "92") (name "Net-(IC5A-X5)") (class "Default")
      (node (ref "IC5") (pin "4") (pinfunction "X5_4") (pintype "input"))
      (node (ref "X21") (pin "4") (pinfunction "S_4") (pintype "passive"))
    )
    (net (code "93") (name "Net-(IC5A-X6)") (class "Default")
      (node (ref "IC5") (pin "3") (pinfunction "X6_3") (pintype "input"))
      (node (ref "X21") (pin "3") (pinfunction "S_3") (pintype "passive"))
    )
    (net (code "94") (name "Net-(IC5A-X7)") (class "Default")
      (node (ref "IC5") (pin "2") (pinfunction "X7_2") (pintype "input"))
      (node (ref "X21") (pin "2") (pinfunction "S_2") (pintype "passive"))
    )
    (net (code "95") (name "Net-(IC5A-X8)") (class "Default")
      (node (ref "IC5") (pin "23") (pinfunction "X8_23") (pintype "input"))
      (node (ref "X22") (pin "11") (pinfunction "S_11") (pintype "passive"))
    )
    (net (code "96") (name "Net-(IC5A-X9)") (class "Default")
      (node (ref "IC5") (pin "22") (pinfunction "X9_22") (pintype "input"))
      (node (ref "X22") (pin "10") (pinfunction "S_10") (pintype "passive"))
    )
    (net (code "97") (name "Net-(IC5A-X10)") (class "Default")
      (node (ref "IC5") (pin "21") (pinfunction "X10_21") (pintype "input"))
      (node (ref "X22") (pin "9") (pinfunction "S_9") (pintype "passive"))
    )
    (net (code "98") (name "Net-(IC5A-X11)") (class "Default")
      (node (ref "IC5") (pin "20") (pinfunction "X11_20") (pintype "input"))
      (node (ref "X22") (pin "8") (pinfunction "S_8") (pintype "passive"))
    )
    (net (code "99") (name "Net-(IC5A-X12)") (class "Default")
      (node (ref "IC5") (pin "19") (pinfunction "X12_19") (pintype "input"))
      (node (ref "X22") (pin "7") (pinfunction "S_7") (pintype "passive"))
    )
    (net (code "100") (name "Net-(IC5A-X13)") (class "Default")
      (node (ref "IC5") (pin "18") (pinfunction "X13_18") (pintype "input"))
      (node (ref "X22") (pin "6") (pinfunction "S_6") (pintype "passive"))
    )
    (net (code "101") (name "Net-(IC5A-X14)") (class "Default")
      (node (ref "IC5") (pin "17") (pinfunction "X14_17") (pintype "input"))
      (node (ref "X22") (pin "5") (pinfunction "S_5") (pintype "passive"))
    )
    (net (code "102") (name "Net-(IC5A-X15)") (class "Default")
      (node (ref "IC5") (pin "16") (pinfunction "X15_16") (pintype "input"))
      (node (ref "X22") (pin "4") (pinfunction "S_4") (pintype "passive"))
    )
    (net (code "103") (name "Net-(IC5B-VDD)") (class "Default")
      (node (ref "IC5") (pin "24") (pinfunction "VDD_24") (pintype "power_in"))
      (node (ref "X22") (pin "12") (pinfunction "S_12") (pintype "passive"))
    )
    (net (code "104") (name "Net-(IC5B-VSS)") (class "Default")
      (node (ref "IC5") (pin "12") (pinfunction "VSS_12") (pintype "power_in"))
      (node (ref "X21") (pin "12") (pinfunction "S_12") (pintype "passive"))
    )
    (net (code "105") (name "Net-(IC6-CD+)") (class "Default")
      (node (ref "IC6") (pin "9") (pinfunction "CD+_9") (pintype "passive"))
      (node (ref "X24") (pin "1") (pinfunction "S_1") (pintype "passive"))
    )
    (net (code "106") (name "Net-(IC6-GND)") (class "Default")
      (node (ref "IC6") (pin "8") (pinfunction "GND_8") (pintype "power_in"))
      (node (ref "X23") (pin "8") (pinfunction "S_8") (pintype "passive"))
    )
    (net (code "107") (name "Net-(IC6-I1)") (class "Default")
      (node (ref "IC6") (pin "1") (pinfunction "I1_1") (pintype "input"))
      (node (ref "X23") (pin "1") (pinfunction "S_1") (pintype "passive"))
    )
    (net (code "108") (name "Net-(IC6-I2)") (class "Default")
      (node (ref "IC6") (pin "2") (pinfunction "I2_2") (pintype "input"))
      (node (ref "X23") (pin "2") (pinfunction "S_2") (pintype "passive"))
    )
    (net (code "109") (name "Net-(IC6-I3)") (class "Default")
      (node (ref "IC6") (pin "3") (pinfunction "I3_3") (pintype "input"))
      (node (ref "X23") (pin "3") (pinfunction "S_3") (pintype "passive"))
    )
    (net (code "110") (name "Net-(IC6-I4)") (class "Default")
      (node (ref "IC6") (pin "4") (pinfunction "I4_4") (pintype "input"))
      (node (ref "X23") (pin "4") (pinfunction "S_4") (pintype "passive"))
    )
    (net (code "111") (name "Net-(IC6-I5)") (class "Default")
      (node (ref "IC6") (pin "5") (pinfunction "I5_5") (pintype "input"))
      (node (ref "X23") (pin "5") (pinfunction "S_5") (pintype "passive"))
    )
    (net (code "112") (name "Net-(IC6-I6)") (class "Default")
      (node (ref "IC6") (pin "6") (pinfunction "I6_6") (pintype "input"))
      (node (ref "X23") (pin "6") (pinfunction "S_6") (pintype "passive"))
    )
    (net (code "113") (name "Net-(IC6-I7)") (class "Default")
      (node (ref "IC6") (pin "7") (pinfunction "I7_7") (pintype "input"))
      (node (ref "X23") (pin "7") (pinfunction "S_7") (pintype "passive"))
    )
    (net (code "114") (name "Net-(IC6-O1)") (class "Default")
      (node (ref "IC6") (pin "16") (pinfunction "O1_16") (pintype "open_collector"))
      (node (ref "X24") (pin "8") (pinfunction "S_8") (pintype "passive"))
    )
    (net (code "115") (name "Net-(IC6-O2)") (class "Default")
      (node (ref "IC6") (pin "15") (pinfunction "O2_15") (pintype "open_collector"))
      (node (ref "X24") (pin "7") (pinfunction "S_7") (pintype "passive"))
    )
    (net (code "116") (name "Net-(IC6-O3)") (class "Default")
      (node (ref "IC6") (pin "14") (pinfunction "O3_14") (pintype "open_collector"))
      (node (ref "X24") (pin "6") (pinfunction "S_6") (pintype "passive"))
    )
    (net (code "117") (name "Net-(IC6-O4)") (class "Default")
      (node (ref "IC6") (pin "13") (pinfunction "O4_13") (pintype "open_collector"))
      (node (ref "X24") (pin "5") (pinfunction "S_5") (pintype "passive"))
    )
    (net (code "118") (name "Net-(IC6-O5)") (class "Default")
      (node (ref "IC6") (pin "12") (pinfunction "O5_12") (pintype "open_collector"))
      (node (ref "X24") (pin "4") (pinfunction "S_4") (pintype "passive"))
    )
    (net (code "119") (name "Net-(IC6-O6)") (class "Default")
      (node (ref "IC6") (pin "11") (pinfunction "O6_11") (pintype "open_collector"))
      (node (ref "X24") (pin "3") (pinfunction "S_3") (pintype "passive"))
    )
    (net (code "120") (name "Net-(IC6-O7)") (class "Default")
      (node (ref "IC6") (pin "10") (pinfunction "O7_10") (pintype "open_collector"))
      (node (ref "X24") (pin "2") (pinfunction "S_2") (pintype "passive"))
    )
    (net (code "121") (name "Net-(IC7A-A)") (class "Default")
      (node (ref "IC7") (pin "10") (pinfunction "A_10") (pintype "input"))
      (node (ref "X31") (pin "10") (pinfunction "S_10") (pintype "passive"))
    )
    (net (code "122") (name "Net-(IC7A-B)") (class "Default")
      (node (ref "IC7") (pin "11") (pinfunction "B_11") (pintype "input"))
      (node (ref "X31") (pin "11") (pinfunction "S_11") (pintype "passive"))
    )
    (net (code "123") (name "Net-(IC7A-C)") (class "Default")
      (node (ref "IC7") (pin "14") (pinfunction "C_14") (pintype "input"))
      (node (ref "X32") (pin "2") (pinfunction "S_2") (pintype "passive"))
    )
    (net (code "124") (name "Net-(IC7A-D)") (class "Default")
      (node (ref "IC7") (pin "13") (pinfunction "D_13") (pintype "input"))
      (node (ref "X32") (pin "1") (pinfunction "S_1") (pintype "passive"))
    )
    (net (code "125") (name "Net-(IC7A-INH)") (class "Default")
      (node (ref "IC7") (pin "15") (pinfunction "INH_15") (pintype "input"))
      (node (ref "X32") (pin "3") (pinfunction "S_3") (pintype "passive"))
    )
    (net (code "126") (name "Net-(IC7A-X)") (class "Default")
      (node (ref "IC7") (pin "1") (pinfunction "X_1") (pintype "output"))
      (node (ref "X31") (pin "1") (pinfunction "S_1") (pintype "passive"))
    )
    (net (code "127") (name "Net-(IC7A-X0)") (class "Default")
      (node (ref "IC7") (pin "9") (pinfunction "X0_9") (pintype "input"))
      (node (ref "X31") (pin "9") (pinfunction "S_9") (pintype "passive"))
    )
    (net (code "128") (name "Net-(IC7A-X1)") (class "Default")
      (node (ref "IC7") (pin "8") (pinfunction "X1_8") (pintype "input"))
      (node (ref "X31") (pin "8") (pinfunction "S_8") (pintype "passive"))
    )
    (net (code "129") (name "Net-(IC7A-X2)") (class "Default")
      (node (ref "IC7") (pin "7") (pinfunction "X2_7") (pintype "input"))
      (node (ref "X31") (pin "7") (pinfunction "S_7") (pintype "passive"))
    )
    (net (code "130") (name "Net-(IC7A-X3)") (class "Default")
      (node (ref "IC7") (pin "6") (pinfunction "X3_6") (pintype "input"))
      (node (ref "X31") (pin "6") (pinfunction "S_6") (pintype "passive"))
    )
    (net (code "131") (name "Net-(IC7A-X4)") (class "Default")
      (node (ref "IC7") (pin "5") (pinfunction "X4_5") (pintype "input"))
      (node (ref "X31") (pin "5") (pinfunction "S_5") (pintype "passive"))
    )
    (net (code "132") (name "Net-(IC7A-X5)") (class "Default")
      (node (ref "IC7") (pin "4") (pinfunction "X5_4") (pintype "input"))
      (node (ref "X31") (pin "4") (pinfunction "S_4") (pintype "passive"))
    )
    (net (code "133") (name "Net-(IC7A-X6)") (class "Default")
      (node (ref "IC7") (pin "3") (pinfunction "X6_3") (pintype "input"))
      (node (ref "X31") (pin "3") (pinfunction "S_3") (pintype "passive"))
    )
    (net (code "134") (name "Net-(IC7A-X7)") (class "Default")
      (node (ref "IC7") (pin "2") (pinfunction "X7_2") (pintype "input"))
      (node (ref "X31") (pin "2") (pinfunction "S_2") (pintype "passive"))
    )
    (net (code "135") (name "Net-(IC7A-X8)") (class "Default")
      (node (ref "IC7") (pin "23") (pinfunction "X8_23") (pintype "input"))
      (node (ref "X32") (pin "11") (pinfunction "S_11") (pintype "passive"))
    )
    (net (code "136") (name "Net-(IC7A-X9)") (class "Default")
      (node (ref "IC7") (pin "22") (pinfunction "X9_22") (pintype "input"))
      (node (ref "X32") (pin "10") (pinfunction "S_10") (pintype "passive"))
    )
    (net (code "137") (name "Net-(IC7A-X10)") (class "Default")
      (node (ref "IC7") (pin "21") (pinfunction "X10_21") (pintype "input"))
      (node (ref "X32") (pin "9") (pinfunction "S_9") (pintype "passive"))
    )
    (net (code "138") (name "Net-(IC7A-X11)") (class "Default")
      (node (ref "IC7") (pin "20") (pinfunction "X11_20") (pintype "input"))
      (node (ref "X32") (pin "8") (pinfunction "S_8") (pintype "passive"))
    )
    (net (code "139") (name "Net-(IC7A-X12)") (class "Default")
      (node (ref "IC7") (pin "19") (pinfunction "X12_19") (pintype "input"))
      (node (ref "X32") (pin "7") (pinfunction "S_7") (pintype "passive"))
    )
    (net (code "140") (name "Net-(IC7A-X13)") (class "Default")
      (node (ref "IC7") (pin "18") (pinfunction "X13_18") (pintype "input"))
      (node (ref "X32") (pin "6") (pinfunction "S_6") (pintype "passive"))
    )
    (net (code "141") (name "Net-(IC7A-X14)") (class "Default")
      (node (ref "IC7") (pin "17") (pinfunction "X14_17") (pintype "input"))
      (node (ref "X32") (pin "5") (pinfunction "S_5") (pintype "passive"))
    )
    (net (code "142") (name "Net-(IC7A-X15)") (class "Default")
      (node (ref "IC7") (pin "16") (pinfunction "X15_16") (pintype "input"))
      (node (ref "X32") (pin "4") (pinfunction "S_4") (pintype "passive"))
    )
    (net (code "143") (name "Net-(IC7B-VDD)") (class "Default")
      (node (ref "IC7") (pin "24") (pinfunction "VDD_24") (pintype "power_in"))
      (node (ref "X32") (pin "12") (pinfunction "S_12") (pintype "passive"))
    )
    (net (code "144") (name "Net-(IC7B-VSS)") (class "Default")
      (node (ref "IC7") (pin "12") (pinfunction "VSS_12") (pintype "power_in"))
      (node (ref "X31") (pin "12") (pinfunction "S_12") (pintype "passive"))
    )
    (net (code "145") (name "Net-(IC8-CD+)") (class "Default")
      (node (ref "IC8") (pin "9") (pinfunction "CD+_9") (pintype "passive"))
      (node (ref "X34") (pin "1") (pinfunction "S_1") (pintype "passive"))
    )
    (net (code "146") (name "Net-(IC8-GND)") (class "Default")
      (node (ref "IC8") (pin "8") (pinfunction "GND_8") (pintype "power_in"))
      (node (ref "X33") (pin "8") (pinfunction "S_8") (pintype "passive"))
    )
    (net (code "147") (name "Net-(IC8-I1)") (class "Default")
      (node (ref "IC8") (pin "1") (pinfunction "I1_1") (pintype "input"))
      (node (ref "X33") (pin "1") (pinfunction "S_1") (pintype "passive"))
    )
    (net (code "148") (name "Net-(IC8-I2)") (class "Default")
      (node (ref "IC8") (pin "2") (pinfunction "I2_2") (pintype "input"))
      (node (ref "X33") (pin "2") (pinfunction "S_2") (pintype "passive"))
    )
    (net (code "149") (name "Net-(IC8-I3)") (class "Default")
      (node (ref "IC8") (pin "3") (pinfunction "I3_3") (pintype "input"))
      (node (ref "X33") (pin "3") (pinfunction "S_3") (pintype "passive"))
    )
    (net (code "150") (name "Net-(IC8-I4)") (class "Default")
      (node (ref "IC8") (pin "4") (pinfunction "I4_4") (pintype "input"))
      (node (ref "X33") (pin "4") (pinfunction "S_4") (pintype "passive"))
    )
    (net (code "151") (name "Net-(IC8-I5)") (class "Default")
      (node (ref "IC8") (pin "5") (pinfunction "I5_5") (pintype "input"))
      (node (ref "X33") (pin "5") (pinfunction "S_5") (pintype "passive"))
    )
    (net (code "152") (name "Net-(IC8-I6)") (class "Default")
      (node (ref "IC8") (pin "6") (pinfunction "I6_6") (pintype "input"))
      (node (ref "X33") (pin "6") (pinfunction "S_6") (pintype "passive"))
    )
    (net (code "153") (name "Net-(IC8-I7)") (class "Default")
      (node (ref "IC8") (pin "7") (pinfunction "I7_7") (pintype "input"))
      (node (ref "X33") (pin "7") (pinfunction "S_7") (pintype "passive"))
    )
    (net (code "154") (name "Net-(IC8-O1)") (class "Default")
      (node (ref "IC8") (pin "16") (pinfunction "O1_16") (pintype "open_collector"))
      (node (ref "X34") (pin "8") (pinfunction "S_8") (pintype "passive"))
    )
    (net (code "155") (name "Net-(IC8-O2)") (class "Default")
      (node (ref "IC8") (pin "15") (pinfunction "O2_15") (pintype "open_collector"))
      (node (ref "X34") (pin "7") (pinfunction "S_7") (pintype "passive"))
    )
    (net (code "156") (name "Net-(IC8-O3)") (class "Default")
      (node (ref "IC8") (pin "14") (pinfunction "O3_14") (pintype "open_collector"))
      (node (ref "X34") (pin "6") (pinfunction "S_6") (pintype "passive"))
    )
    (net (code "157") (name "Net-(IC8-O4)") (class "Default")
      (node (ref "IC8") (pin "13") (pinfunction "O4_13") (pintype "open_collector"))
      (node (ref "X34") (pin "5") (pinfunction "S_5") (pintype "passive"))
    )
    (net (code "158") (name "Net-(IC8-O5)") (class "Default")
      (node (ref "IC8") (pin "12") (pinfunction "O5_12") (pintype "open_collector"))
      (node (ref "X34") (pin "4") (pinfunction "S_4") (pintype "passive"))
    )
    (net (code "159") (name "Net-(IC8-O6)") (class "Default")
      (node (ref "IC8") (pin "11") (pinfunction "O6_11") (pintype "open_collector"))
      (node (ref "X34") (pin "3") (pinfunction "S_3") (pintype "passive"))
    )
    (net (code "160") (name "Net-(IC8-O7)") (class "Default")
      (node (ref "IC8") (pin "10") (pinfunction "O7_10") (pintype "open_collector"))
      (node (ref "X34") (pin "2") (pinfunction "S_2") (pintype "passive"))
    )
    (net (code "161") (name "Net-(IC9A-A)") (class "Default")
      (node (ref "IC9") (pin "10") (pinfunction "A_10") (pintype "input"))
      (node (ref "X41") (pin "10") (pinfunction "S_10") (pintype "passive"))
    )
    (net (code "162") (name "Net-(IC9A-B)") (class "Default")
      (node (ref "IC9") (pin "11") (pinfunction "B_11") (pintype "input"))
      (node (ref "X41") (pin "11") (pinfunction "S_11") (pintype "passive"))
    )
    (net (code "163") (name "Net-(IC9A-C)") (class "Default")
      (node (ref "IC9") (pin "14") (pinfunction "C_14") (pintype "input"))
      (node (ref "X42") (pin "2") (pinfunction "S_2") (pintype "passive"))
    )
    (net (code "164") (name "Net-(IC9A-D)") (class "Default")
      (node (ref "IC9") (pin "13") (pinfunction "D_13") (pintype "input"))
      (node (ref "X42") (pin "1") (pinfunction "S_1") (pintype "passive"))
    )
    (net (code "165") (name "Net-(IC9A-INH)") (class "Default")
      (node (ref "IC9") (pin "15") (pinfunction "INH_15") (pintype "input"))
      (node (ref "X42") (pin "3") (pinfunction "S_3") (pintype "passive"))
    )
    (net (code "166") (name "Net-(IC9A-X)") (class "Default")
      (node (ref "IC9") (pin "1") (pinfunction "X_1") (pintype "output"))
      (node (ref "X41") (pin "1") (pinfunction "S_1") (pintype "passive"))
    )
    (net (code "167") (name "Net-(IC9A-X0)") (class "Default")
      (node (ref "IC9") (pin "9") (pinfunction "X0_9") (pintype "input"))
      (node (ref "X41") (pin "9") (pinfunction "S_9") (pintype "passive"))
    )
    (net (code "168") (name "Net-(IC9A-X1)") (class "Default")
      (node (ref "IC9") (pin "8") (pinfunction "X1_8") (pintype "input"))
      (node (ref "X41") (pin "8") (pinfunction "S_8") (pintype "passive"))
    )
    (net (code "169") (name "Net-(IC9A-X2)") (class "Default")
      (node (ref "IC9") (pin "7") (pinfunction "X2_7") (pintype "input"))
      (node (ref "X41") (pin "7") (pinfunction "S_7") (pintype "passive"))
    )
    (net (code "170") (name "Net-(IC9A-X3)") (class "Default")
      (node (ref "IC9") (pin "6") (pinfunction "X3_6") (pintype "input"))
      (node (ref "X41") (pin "6") (pinfunction "S_6") (pintype "passive"))
    )
    (net (code "171") (name "Net-(IC9A-X4)") (class "Default")
      (node (ref "IC9") (pin "5") (pinfunction "X4_5") (pintype "input"))
      (node (ref "X41") (pin "5") (pinfunction "S_5") (pintype "passive"))
    )
    (net (code "172") (name "Net-(IC9A-X5)") (class "Default")
      (node (ref "IC9") (pin "4") (pinfunction "X5_4") (pintype "input"))
      (node (ref "X41") (pin "4") (pinfunction "S_4") (pintype "passive"))
    )
    (net (code "173") (name "Net-(IC9A-X6)") (class "Default")
      (node (ref "IC9") (pin "3") (pinfunction "X6_3") (pintype "input"))
      (node (ref "X41") (pin "3") (pinfunction "S_3") (pintype "passive"))
    )
    (net (code "174") (name "Net-(IC9A-X7)") (class "Default")
      (node (ref "IC9") (pin "2") (pinfunction "X7_2") (pintype "input"))
      (node (ref "X41") (pin "2") (pinfunction "S_2") (pintype "passive"))
    )
    (net (code "175") (name "Net-(IC9A-X8)") (class "Default")
      (node (ref "IC9") (pin "23") (pinfunction "X8_23") (pintype "input"))
      (node (ref "X42") (pin "11") (pinfunction "S_11") (pintype "passive"))
    )
    (net (code "176") (name "Net-(IC9A-X9)") (class "Default")
      (node (ref "IC9") (pin "22") (pinfunction "X9_22") (pintype "input"))
      (node (ref "X42") (pin "10") (pinfunction "S_10") (pintype "passive"))
    )
    (net (code "177") (name "Net-(IC9A-X10)") (class "Default")
      (node (ref "IC9") (pin "21") (pinfunction "X10_21") (pintype "input"))
      (node (ref "X42") (pin "9") (pinfunction "S_9") (pintype "passive"))
    )
    (net (code "178") (name "Net-(IC9A-X11)") (class "Default")
      (node (ref "IC9") (pin "20") (pinfunction "X11_20") (pintype "input"))
      (node (ref "X42") (pin "8") (pinfunction "S_8") (pintype "passive"))
    )
    (net (code "179") (name "Net-(IC9A-X12)") (class "Default")
      (node (ref "IC9") (pin "19") (pinfunction "X12_19") (pintype "input"))
      (node (ref "X42") (pin "7") (pinfunction "S_7") (pintype "passive"))
    )
    (net (code "180") (name "Net-(IC9A-X13)") (class "Default")
      (node (ref "IC9") (pin "18") (pinfunction "X13_18") (pintype "input"))
      (node (ref "X42") (pin "6") (pinfunction "S_6") (pintype "passive"))
    )
    (net (code "181") (name "Net-(IC9A-X14)") (class "Default")
      (node (ref "IC9") (pin "17") (pinfunction "X14_17") (pintype "input"))
      (node (ref "X42") (pin "5") (pinfunction "S_5") (pintype "passive"))
    )
    (net (code "182") (name "Net-(IC9A-X15)") (class "Default")
      (node (ref "IC9") (pin "16") (pinfunction "X15_16") (pintype "input"))
      (node (ref "X42") (pin "4") (pinfunction "S_4") (pintype "passive"))
    )
    (net (code "183") (name "Net-(IC9B-VDD)") (class "Default")
      (node (ref "IC9") (pin "24") (pinfunction "VDD_24") (pintype "power_in"))
      (node (ref "X42") (pin "12") (pinfunction "S_12") (pintype "passive"))
    )
    (net (code "184") (name "Net-(IC9B-VSS)") (class "Default")
      (node (ref "IC9") (pin "12") (pinfunction "VSS_12") (pintype "power_in"))
      (node (ref "X41") (pin "12") (pinfunction "S_12") (pintype "passive"))
    )
    (net (code "185") (name "Net-(IC10-CD+)") (class "Default")
      (node (ref "IC10") (pin "9") (pinfunction "CD+_9") (pintype "passive"))
      (node (ref "X44") (pin "1") (pinfunction "S_1") (pintype "passive"))
    )
    (net (code "186") (name "Net-(IC10-GND)") (class "Default")
      (node (ref "IC10") (pin "8") (pinfunction "GND_8") (pintype "power_in"))
      (node (ref "X43") (pin "8") (pinfunction "S_8") (pintype "passive"))
    )
    (net (code "187") (name "Net-(IC10-I1)") (class "Default")
      (node (ref "IC10") (pin "1") (pinfunction "I1_1") (pintype "input"))
      (node (ref "X43") (pin "1") (pinfunction "S_1") (pintype "passive"))
    )
    (net (code "188") (name "Net-(IC10-I2)") (class "Default")
      (node (ref "IC10") (pin "2") (pinfunction "I2_2") (pintype "input"))
      (node (ref "X43") (pin "2") (pinfunction "S_2") (pintype "passive"))
    )
    (net (code "189") (name "Net-(IC10-I3)") (class "Default")
      (node (ref "IC10") (pin "3") (pinfunction "I3_3") (pintype "input"))
      (node (ref "X43") (pin "3") (pinfunction "S_3") (pintype "passive"))
    )
    (net (code "190") (name "Net-(IC10-I4)") (class "Default")
      (node (ref "IC10") (pin "4") (pinfunction "I4_4") (pintype "input"))
      (node (ref "X43") (pin "4") (pinfunction "S_4") (pintype "passive"))
    )
    (net (code "191") (name "Net-(IC10-I5)") (class "Default")
      (node (ref "IC10") (pin "5") (pinfunction "I5_5") (pintype "input"))
      (node (ref "X43") (pin "5") (pinfunction "S_5") (pintype "passive"))
    )
    (net (code "192") (name "Net-(IC10-I6)") (class "Default")
      (node (ref "IC10") (pin "6") (pinfunction "I6_6") (pintype "input"))
      (node (ref "X43") (pin "6") (pinfunction "S_6") (pintype "passive"))
    )
    (net (code "193") (name "Net-(IC10-I7)") (class "Default")
      (node (ref "IC10") (pin "7") (pinfunction "I7_7") (pintype "input"))
      (node (ref "X43") (pin "7") (pinfunction "S_7") (pintype "passive"))
    )
    (net (code "194") (name "Net-(IC10-O1)") (class "Default")
      (node (ref "IC10") (pin "16") (pinfunction "O1_16") (pintype "open_collector"))
      (node (ref "X44") (pin "8") (pinfunction "S_8") (pintype "passive"))
    )
    (net (code "195") (name "Net-(IC10-O2)") (class "Default")
      (node (ref "IC10") (pin "15") (pinfunction "O2_15") (pintype "open_collector"))
      (node (ref "X44") (pin "7") (pinfunction "S_7") (pintype "passive"))
    )
    (net (code "196") (name "Net-(IC10-O3)") (class "Default")
      (node (ref "IC10") (pin "14") (pinfunction "O3_14") (pintype "open_collector"))
      (node (ref "X44") (pin "6") (pinfunction "S_6") (pintype "passive"))
    )
    (net (code "197") (name "Net-(IC10-O4)") (class "Default")
      (node (ref "IC10") (pin "13") (pinfunction "O4_13") (pintype "open_collector"))
      (node (ref "X44") (pin "5") (pinfunction "S_5") (pintype "passive"))
    )
    (net (code "198") (name "Net-(IC10-O5)") (class "Default")
      (node (ref "IC10") (pin "12") (pinfunction "O5_12") (pintype "open_collector"))
      (node (ref "X44") (pin "4") (pinfunction "S_4") (pintype "passive"))
    )
    (net (code "199") (name "Net-(IC10-O6)") (class "Default")
      (node (ref "IC10") (pin "11") (pinfunction "O6_11") (pintype "open_collector"))
      (node (ref "X44") (pin "3") (pinfunction "S_3") (pintype "passive"))
    )
    (net (code "200") (name "Net-(IC10-O7)") (class "Default")
      (node (ref "IC10") (pin "10") (pinfunction "O7_10") (pintype "open_collector"))
      (node (ref "X44") (pin "2") (pinfunction "S_2") (pintype "passive"))
    )
    (net (code "201") (name "Net-(IC11A-A)") (class "Default")
      (node (ref "IC11") (pin "10") (pinfunction "A_10") (pintype "input"))
      (node (ref "X51") (pin "10") (pinfunction "S_10") (pintype "passive"))
    )
    (net (code "202") (name "Net-(IC11A-B)") (class "Default")
      (node (ref "IC11") (pin "11") (pinfunction "B_11") (pintype "input"))
      (node (ref "X51") (pin "11") (pinfunction "S_11") (pintype "passive"))
    )
    (net (code "203") (name "Net-(IC11A-C)") (class "Default")
      (node (ref "IC11") (pin "14") (pinfunction "C_14") (pintype "input"))
      (node (ref "X52") (pin "2") (pinfunction "S_2") (pintype "passive"))
    )
    (net (code "204") (name "Net-(IC11A-D)") (class "Default")
      (node (ref "IC11") (pin "13") (pinfunction "D_13") (pintype "input"))
      (node (ref "X52") (pin "1") (pinfunction "S_1") (pintype "passive"))
    )
    (net (code "205") (name "Net-(IC11A-INH)") (class "Default")
      (node (ref "IC11") (pin "15") (pinfunction "INH_15") (pintype "input"))
      (node (ref "X52") (pin "3") (pinfunction "S_3") (pintype "passive"))
    )
    (net (code "206") (name "Net-(IC11A-X)") (class "Default")
      (node (ref "IC11") (pin "1") (pinfunction "X_1") (pintype "output"))
      (node (ref "X51") (pin "1") (pinfunction "S_1") (pintype "passive"))
    )
    (net (code "207") (name "Net-(IC11A-X0)") (class "Default")
      (node (ref "IC11") (pin "9") (pinfunction "X0_9") (pintype "input"))
      (node (ref "X51") (pin "9") (pinfunction "S_9") (pintype "passive"))
    )
    (net (code "208") (name "Net-(IC11A-X1)") (class "Default")
      (node (ref "IC11") (pin "8") (pinfunction "X1_8") (pintype "input"))
      (node (ref "X51") (pin "8") (pinfunction "S_8") (pintype "passive"))
    )
    (net (code "209") (name "Net-(IC11A-X2)") (class "Default")
      (node (ref "IC11") (pin "7") (pinfunction "X2_7") (pintype "input"))
      (node (ref "X51") (pin "7") (pinfunction "S_7") (pintype "passive"))
    )
    (net (code "210") (name "Net-(IC11A-X3)") (class "Default")
      (node (ref "IC11") (pin "6") (pinfunction "X3_6") (pintype "input"))
      (node (ref "X51") (pin "6") (pinfunction "S_6") (pintype "passive"))
    )
    (net (code "211") (name "Net-(IC11A-X4)") (class "Default")
      (node (ref "IC11") (pin "5") (pinfunction "X4_5") (pintype "input"))
      (node (ref "X51") (pin "5") (pinfunction "S_5") (pintype "passive"))
    )
    (net (code "212") (name "Net-(IC11A-X5)") (class "Default")
      (node (ref "IC11") (pin "4") (pinfunction "X5_4") (pintype "input"))
      (node (ref "X51") (pin "4") (pinfunction "S_4") (pintype "passive"))
    )
    (net (code "213") (name "Net-(IC11A-X6)") (class "Default")
      (node (ref "IC11") (pin "3") (pinfunction "X6_3") (pintype "input"))
      (node (ref "X51") (pin "3") (pinfunction "S_3") (pintype "passive"))
    )
    (net (code "214") (name "Net-(IC11A-X7)") (class "Default")
      (node (ref "IC11") (pin "2") (pinfunction "X7_2") (pintype "input"))
      (node (ref "X51") (pin "2") (pinfunction "S_2") (pintype "passive"))
    )
    (net (code "215") (name "Net-(IC11A-X8)") (class "Default")
      (node (ref "IC11") (pin "23") (pinfunction "X8_23") (pintype "input"))
      (node (ref "X52") (pin "11") (pinfunction "S_11") (pintype "passive"))
    )
    (net (code "216") (name "Net-(IC11A-X9)") (class "Default")
      (node (ref "IC11") (pin "22") (pinfunction "X9_22") (pintype "input"))
      (node (ref "X52") (pin "10") (pinfunction "S_10") (pintype "passive"))
    )
    (net (code "217") (name "Net-(IC11A-X10)") (class "Default")
      (node (ref "IC11") (pin "21") (pinfunction "X10_21") (pintype "input"))
      (node (ref "X52") (pin "9") (pinfunction "S_9") (pintype "passive"))
    )
    (net (code "218") (name "Net-(IC11A-X11)") (class "Default")
      (node (ref "IC11") (pin "20") (pinfunction "X11_20") (pintype "input"))
      (node (ref "X52") (pin "8") (pinfunction "S_8") (pintype "passive"))
    )
    (net (code "219") (name "Net-(IC11A-X12)") (class "Default")
      (node (ref "IC11") (pin "19") (pinfunction "X12_19") (pintype "input"))
      (node (ref "X52") (pin "7") (pinfunction "S_7") (pintype "passive"))
    )
    (net (code "220") (name "Net-(IC11A-X13)") (class "Default")
      (node (ref "IC11") (pin "18") (pinfunction "X13_18") (pintype "input"))
      (node (ref "X52") (pin "6") (pinfunction "S_6") (pintype "passive"))
    )
    (net (code "221") (name "Net-(IC11A-X14)") (class "Default")
      (node (ref "IC11") (pin "17") (pinfunction "X14_17") (pintype "input"))
      (node (ref "X52") (pin "5") (pinfunction "S_5") (pintype "passive"))
    )
    (net (code "222") (name "Net-(IC11A-X15)") (class "Default")
      (node (ref "IC11") (pin "16") (pinfunction "X15_16") (pintype "input"))
      (node (ref "X52") (pin "4") (pinfunction "S_4") (pintype "passive"))
    )
    (net (code "223") (name "Net-(IC11B-VDD)") (class "Default")
      (node (ref "IC11") (pin "24") (pinfunction "VDD_24") (pintype "power_in"))
      (node (ref "X52") (pin "12") (pinfunction "S_12") (pintype "passive"))
    )
    (net (code "224") (name "Net-(IC11B-VSS)") (class "Default")
      (node (ref "IC11") (pin "12") (pinfunction "VSS_12") (pintype "power_in"))
      (node (ref "X51") (pin "12") (pinfunction "S_12") (pintype "passive"))
    )
    (net (code "225") (name "Net-(IC12-CD+)") (class "Default")
      (node (ref "IC12") (pin "9") (pinfunction "CD+_9") (pintype "passive"))
      (node (ref "X54") (pin "1") (pinfunction "S_1") (pintype "passive"))
    )
    (net (code "226") (name "Net-(IC12-GND)") (class "Default")
      (node (ref "IC12") (pin "8") (pinfunction "GND_8") (pintype "power_in"))
      (node (ref "X53") (pin "8") (pinfunction "S_8") (pintype "passive"))
    )
    (net (code "227") (name "Net-(IC12-I1)") (class "Default")
      (node (ref "IC12") (pin "1") (pinfunction "I1_1") (pintype "input"))
      (node (ref "X53") (pin "1") (pinfunction "S_1") (pintype "passive"))
    )
    (net (code "228") (name "Net-(IC12-I2)") (class "Default")
      (node (ref "IC12") (pin "2") (pinfunction "I2_2") (pintype "input"))
      (node (ref "X53") (pin "2") (pinfunction "S_2") (pintype "passive"))
    )
    (net (code "229") (name "Net-(IC12-I3)") (class "Default")
      (node (ref "IC12") (pin "3") (pinfunction "I3_3") (pintype "input"))
      (node (ref "X53") (pin "3") (pinfunction "S_3") (pintype "passive"))
    )
    (net (code "230") (name "Net-(IC12-I4)") (class "Default")
      (node (ref "IC12") (pin "4") (pinfunction "I4_4") (pintype "input"))
      (node (ref "X53") (pin "4") (pinfunction "S_4") (pintype "passive"))
    )
    (net (code "231") (name "Net-(IC12-I5)") (class "Default")
      (node (ref "IC12") (pin "5") (pinfunction "I5_5") (pintype "input"))
      (node (ref "X53") (pin "5") (pinfunction "S_5") (pintype "passive"))
    )
    (net (code "232") (name "Net-(IC12-I6)") (class "Default")
      (node (ref "IC12") (pin "6") (pinfunction "I6_6") (pintype "input"))
      (node (ref "X53") (pin "6") (pinfunction "S_6") (pintype "passive"))
    )
    (net (code "233") (name "Net-(IC12-I7)") (class "Default")
      (node (ref "IC12") (pin "7") (pinfunction "I7_7") (pintype "input"))
      (node (ref "X53") (pin "7") (pinfunction "S_7") (pintype "passive"))
    )
    (net (code "234") (name "Net-(IC12-O1)") (class "Default")
      (node (ref "IC12") (pin "16") (pinfunction "O1_16") (pintype "open_collector"))
      (node (ref "X54") (pin "8") (pinfunction "S_8") (pintype "passive"))
    )
    (net (code "235") (name "Net-(IC12-O2)") (class "Default")
      (node (ref "IC12") (pin "15") (pinfunction "O2_15") (pintype "open_collector"))
      (node (ref "X54") (pin "7") (pinfunction "S_7") (pintype "passive"))
    )
    (net (code "236") (name "Net-(IC12-O3)") (class "Default")
      (node (ref "IC12") (pin "14") (pinfunction "O3_14") (pintype "open_collector"))
      (node (ref "X54") (pin "6") (pinfunction "S_6") (pintype "passive"))
    )
    (net (code "237") (name "Net-(IC12-O4)") (class "Default")
      (node (ref "IC12") (pin "13") (pinfunction "O4_13") (pintype "open_collector"))
      (node (ref "X54") (pin "5") (pinfunction "S_5") (pintype "passive"))
    )
    (net (code "238") (name "Net-(IC12-O5)") (class "Default")
      (node (ref "IC12") (pin "12") (pinfunction "O5_12") (pintype "open_collector"))
      (node (ref "X54") (pin "4") (pinfunction "S_4") (pintype "passive"))
    )
    (net (code "239") (name "Net-(IC12-O6)") (class "Default")
      (node (ref "IC12") (pin "11") (pinfunction "O6_11") (pintype "open_collector"))
      (node (ref "X54") (pin "3") (pinfunction "S_3") (pintype "passive"))
    )
    (net (code "240") (name "Net-(IC12-O7)") (class "Default")
      (node (ref "IC12") (pin "10") (pinfunction "O7_10") (pintype "open_collector"))
      (node (ref "X54") (pin "2") (pinfunction "S_2") (pintype "passive"))
    )
    (net (code "241") (name "Net-(IC13A-A)") (class "Default")
      (node (ref "IC13") (pin "10") (pinfunction "A_10") (pintype "input"))
      (node (ref "X61") (pin "10") (pinfunction "S_10") (pintype "passive"))
    )
    (net (code "242") (name "Net-(IC13A-B)") (class "Default")
      (node (ref "IC13") (pin "11") (pinfunction "B_11") (pintype "input"))
      (node (ref "X61") (pin "11") (pinfunction "S_11") (pintype "passive"))
    )
    (net (code "243") (name "Net-(IC13A-C)") (class "Default")
      (node (ref "IC13") (pin "14") (pinfunction "C_14") (pintype "input"))
      (node (ref "X62") (pin "2") (pinfunction "S_2") (pintype "passive"))
    )
    (net (code "244") (name "Net-(IC13A-D)") (class "Default")
      (node (ref "IC13") (pin "13") (pinfunction "D_13") (pintype "input"))
      (node (ref "X62") (pin "1") (pinfunction "S_1") (pintype "passive"))
    )
    (net (code "245") (name "Net-(IC13A-INH)") (class "Default")
      (node (ref "IC13") (pin "15") (pinfunction "INH_15") (pintype "input"))
      (node (ref "X62") (pin "3") (pinfunction "S_3") (pintype "passive"))
    )
    (net (code "246") (name "Net-(IC13A-X)") (class "Default")
      (node (ref "IC13") (pin "1") (pinfunction "X_1") (pintype "output"))
      (node (ref "X61") (pin "1") (pinfunction "S_1") (pintype "passive"))
    )
    (net (code "247") (name "Net-(IC13A-X0)") (class "Default")
      (node (ref "IC13") (pin "9") (pinfunction "X0_9") (pintype "input"))
      (node (ref "X61") (pin "9") (pinfunction "S_9") (pintype "passive"))
    )
    (net (code "248") (name "Net-(IC13A-X1)") (class "Default")
      (node (ref "IC13") (pin "8") (pinfunction "X1_8") (pintype "input"))
      (node (ref "X61") (pin "8") (pinfunction "S_8") (pintype "passive"))
    )
    (net (code "249") (name "Net-(IC13A-X2)") (class "Default")
      (node (ref "IC13") (pin "7") (pinfunction "X2_7") (pintype "input"))
      (node (ref "X61") (pin "7") (pinfunction "S_7") (pintype "passive"))
    )
    (net (code "250") (name "Net-(IC13A-X3)") (class "Default")
      (node (ref "IC13") (pin "6") (pinfunction "X3_6") (pintype "input"))
      (node (ref "X61") (pin "6") (pinfunction "S_6") (pintype "passive"))
    )
    (net (code "251") (name "Net-(IC13A-X4)") (class "Default")
      (node (ref "IC13") (pin "5") (pinfunction "X4_5") (pintype "input"))
      (node (ref "X61") (pin "5") (pinfunction "S_5") (pintype "passive"))
    )
    (net (code "252") (name "Net-(IC13A-X5)") (class "Default")
      (node (ref "IC13") (pin "4") (pinfunction "X5_4") (pintype "input"))
      (node (ref "X61") (pin "4") (pinfunction "S_4") (pintype "passive"))
    )
    (net (code "253") (name "Net-(IC13A-X6)") (class "Default")
      (node (ref "IC13") (pin "3") (pinfunction "X6_3") (pintype "input"))
      (node (ref "X61") (pin "3") (pinfunction "S_3") (pintype "passive"))
    )
    (net (code "254") (name "Net-(IC13A-X7)") (class "Default")
      (node (ref "IC13") (pin "2") (pinfunction "X7_2") (pintype "input"))
      (node (ref "X61") (pin "2") (pinfunction "S_2") (pintype "passive"))
    )
    (net (code "255") (name "Net-(IC13A-X8)") (class "Default")
      (node (ref "IC13") (pin "23") (pinfunction "X8_23") (pintype "input"))
      (node (ref "X62") (pin "11") (pinfunction "S_11") (pintype "passive"))
    )
    (net (code "256") (name "Net-(IC13A-X9)") (class "Default")
      (node (ref "IC13") (pin "22") (pinfunction "X9_22") (pintype "input"))
      (node (ref "X62") (pin "10") (pinfunction "S_10") (pintype "passive"))
    )
    (net (code "257") (name "Net-(IC13A-X10)") (class "Default")
      (node (ref "IC13") (pin "21") (pinfunction "X10_21") (pintype "input"))
      (node (ref "X62") (pin "9") (pinfunction "S_9") (pintype "passive"))
    )
    (net (code "258") (name "Net-(IC13A-X11)") (class "Default")
      (node (ref "IC13") (pin "20") (pinfunction "X11_20") (pintype "input"))
      (node (ref "X62") (pin "8") (pinfunction "S_8") (pintype "passive"))
    )
    (net (code "259") (name "Net-(IC13A-X12)") (class "Default")
      (node (ref "IC13") (pin "19") (pinfunction "X12_19") (pintype "input"))
      (node (ref "X62") (pin "7") (pinfunction "S_7") (pintype "passive"))
    )
    (net (code "260") (name "Net-(IC13A-X13)") (class "Default")
      (node (ref "IC13") (pin "18") (pinfunction "X13_18") (pintype "input"))
      (node (ref "X62") (pin "6") (pinfunction "S_6") (pintype "passive"))
    )
    (net (code "261") (name "Net-(IC13A-X14)") (class "Default")
      (node (ref "IC13") (pin "17") (pinfunction "X14_17") (pintype "input"))
      (node (ref "X62") (pin "5") (pinfunction "S_5") (pintype "passive"))
    )
    (net (code "262") (name "Net-(IC13A-X15)") (class "Default")
      (node (ref "IC13") (pin "16") (pinfunction "X15_16") (pintype "input"))
      (node (ref "X62") (pin "4") (pinfunction "S_4") (pintype "passive"))
    )
    (net (code "263") (name "Net-(IC13B-VDD)") (class "Default")
      (node (ref "IC13") (pin "24") (pinfunction "VDD_24") (pintype "power_in"))
      (node (ref "X62") (pin "12") (pinfunction "S_12") (pintype "passive"))
    )
    (net (code "264") (name "Net-(IC13B-VSS)") (class "Default")
      (node (ref "IC13") (pin "12") (pinfunction "VSS_12") (pintype "power_in"))
      (node (ref "X61") (pin "12") (pinfunction "S_12") (pintype "passive"))
    )
    (net (code "265") (name "Net-(IC14-CD+)") (class "Default")
      (node (ref "IC14") (pin "9") (pinfunction "CD+_9") (pintype "passive"))
      (node (ref "X64") (pin "1") (pinfunction "S_1") (pintype "passive"))
    )
    (net (code "266") (name "Net-(IC14-GND)") (class "Default")
      (node (ref "IC14") (pin "8") (pinfunction "GND_8") (pintype "power_in"))
      (node (ref "X63") (pin "8") (pinfunction "S_8") (pintype "passive"))
    )
    (net (code "267") (name "Net-(IC14-I1)") (class "Default")
      (node (ref "IC14") (pin "1") (pinfunction "I1_1") (pintype "input"))
      (node (ref "X63") (pin "1") (pinfunction "S_1") (pintype "passive"))
    )
    (net (code "268") (name "Net-(IC14-I2)") (class "Default")
      (node (ref "IC14") (pin "2") (pinfunction "I2_2") (pintype "input"))
      (node (ref "X63") (pin "2") (pinfunction "S_2") (pintype "passive"))
    )
    (net (code "269") (name "Net-(IC14-I3)") (class "Default")
      (node (ref "IC14") (pin "3") (pinfunction "I3_3") (pintype "input"))
      (node (ref "X63") (pin "3") (pinfunction "S_3") (pintype "passive"))
    )
    (net (code "270") (name "Net-(IC14-I4)") (class "Default")
      (node (ref "IC14") (pin "4") (pinfunction "I4_4") (pintype "input"))
      (node (ref "X63") (pin "4") (pinfunction "S_4") (pintype "passive"))
    )
    (net (code "271") (name "Net-(IC14-I5)") (class "Default")
      (node (ref "IC14") (pin "5") (pinfunction "I5_5") (pintype "input"))
      (node (ref "X63") (pin "5") (pinfunction "S_5") (pintype "passive"))
    )
    (net (code "272") (name "Net-(IC14-I6)") (class "Default")
      (node (ref "IC14") (pin "6") (pinfunction "I6_6") (pintype "input"))
      (node (ref "X63") (pin "6") (pinfunction "S_6") (pintype "passive"))
    )
    (net (code "273") (name "Net-(IC14-I7)") (class "Default")
      (node (ref "IC14") (pin "7") (pinfunction "I7_7") (pintype "input"))
      (node (ref "X63") (pin "7") (pinfunction "S_7") (pintype "passive"))
    )
    (net (code "274") (name "Net-(IC14-O1)") (class "Default")
      (node (ref "IC14") (pin "16") (pinfunction "O1_16") (pintype "open_collector"))
      (node (ref "X64") (pin "8") (pinfunction "S_8") (pintype "passive"))
    )
    (net (code "275") (name "Net-(IC14-O2)") (class "Default")
      (node (ref "IC14") (pin "15") (pinfunction "O2_15") (pintype "open_collector"))
      (node (ref "X64") (pin "7") (pinfunction "S_7") (pintype "passive"))
    )
    (net (code "276") (name "Net-(IC14-O3)") (class "Default")
      (node (ref "IC14") (pin "14") (pinfunction "O3_14") (pintype "open_collector"))
      (node (ref "X64") (pin "6") (pinfunction "S_6") (pintype "passive"))
    )
    (net (code "277") (name "Net-(IC14-O4)") (class "Default")
      (node (ref "IC14") (pin "13") (pinfunction "O4_13") (pintype "open_collector"))
      (node (ref "X64") (pin "5") (pinfunction "S_5") (pintype "passive"))
    )
    (net (code "278") (name "Net-(IC14-O5)") (class "Default")
      (node (ref "IC14") (pin "12") (pinfunction "O5_12") (pintype "open_collector"))
      (node (ref "X64") (pin "4") (pinfunction "S_4") (pintype "passive"))
    )
    (net (code "279") (name "Net-(IC14-O6)") (class "Default")
      (node (ref "IC14") (pin "11") (pinfunction "O6_11") (pintype "open_collector"))
      (node (ref "X64") (pin "3") (pinfunction "S_3") (pintype "passive"))
    )
    (net (code "280") (name "Net-(IC14-O7)") (class "Default")
      (node (ref "IC14") (pin "10") (pinfunction "O7_10") (pintype "open_collector"))
      (node (ref "X64") (pin "2") (pinfunction "S_2") (pintype "passive"))
    )
    (net (code "281") (name "Net-(IC15A-A)") (class "Default")
      (node (ref "IC15") (pin "10") (pinfunction "A_10") (pintype "input"))
      (node (ref "X71") (pin "10") (pinfunction "S_10") (pintype "passive"))
    )
    (net (code "282") (name "Net-(IC15A-B)") (class "Default")
      (node (ref "IC15") (pin "11") (pinfunction "B_11") (pintype "input"))
      (node (ref "X71") (pin "11") (pinfunction "S_11") (pintype "passive"))
    )
    (net (code "283") (name "Net-(IC15A-C)") (class "Default")
      (node (ref "IC15") (pin "14") (pinfunction "C_14") (pintype "input"))
      (node (ref "X72") (pin "2") (pinfunction "S_2") (pintype "passive"))
    )
    (net (code "284") (name "Net-(IC15A-D)") (class "Default")
      (node (ref "IC15") (pin "13") (pinfunction "D_13") (pintype "input"))
      (node (ref "X72") (pin "1") (pinfunction "S_1") (pintype "passive"))
    )
    (net (code "285") (name "Net-(IC15A-INH)") (class "Default")
      (node (ref "IC15") (pin "15") (pinfunction "INH_15") (pintype "input"))
      (node (ref "X72") (pin "3") (pinfunction "S_3") (pintype "passive"))
    )
    (net (code "286") (name "Net-(IC15A-X)") (class "Default")
      (node (ref "IC15") (pin "1") (pinfunction "X_1") (pintype "output"))
      (node (ref "X71") (pin "1") (pinfunction "S_1") (pintype "passive"))
    )
    (net (code "287") (name "Net-(IC15A-X0)") (class "Default")
      (node (ref "IC15") (pin "9") (pinfunction "X0_9") (pintype "input"))
      (node (ref "X71") (pin "9") (pinfunction "S_9") (pintype "passive"))
    )
    (net (code "288") (name "Net-(IC15A-X1)") (class "Default")
      (node (ref "IC15") (pin "8") (pinfunction "X1_8") (pintype "input"))
      (node (ref "X71") (pin "8") (pinfunction "S_8") (pintype "passive"))
    )
    (net (code "289") (name "Net-(IC15A-X2)") (class "Default")
      (node (ref "IC15") (pin "7") (pinfunction "X2_7") (pintype "input"))
      (node (ref "X71") (pin "7") (pinfunction "S_7") (pintype "passive"))
    )
    (net (code "290") (name "Net-(IC15A-X3)") (class "Default")
      (node (ref "IC15") (pin "6") (pinfunction "X3_6") (pintype "input"))
      (node (ref "X71") (pin "6") (pinfunction "S_6") (pintype "passive"))
    )
    (net (code "291") (name "Net-(IC15A-X4)") (class "Default")
      (node (ref "IC15") (pin "5") (pinfunction "X4_5") (pintype "input"))
      (node (ref "X71") (pin "5") (pinfunction "S_5") (pintype "passive"))
    )
    (net (code "292") (name "Net-(IC15A-X5)") (class "Default")
      (node (ref "IC15") (pin "4") (pinfunction "X5_4") (pintype "input"))
      (node (ref "X71") (pin "4") (pinfunction "S_4") (pintype "passive"))
    )
    (net (code "293") (name "Net-(IC15A-X6)") (class "Default")
      (node (ref "IC15") (pin "3") (pinfunction "X6_3") (pintype "input"))
      (node (ref "X71") (pin "3") (pinfunction "S_3") (pintype "passive"))
    )
    (net (code "294") (name "Net-(IC15A-X7)") (class "Default")
      (node (ref "IC15") (pin "2") (pinfunction "X7_2") (pintype "input"))
      (node (ref "X71") (pin "2") (pinfunction "S_2") (pintype "passive"))
    )
    (net (code "295") (name "Net-(IC15A-X8)") (class "Default")
      (node (ref "IC15") (pin "23") (pinfunction "X8_23") (pintype "input"))
      (node (ref "X72") (pin "11") (pinfunction "S_11") (pintype "passive"))
    )
    (net (code "296") (name "Net-(IC15A-X9)") (class "Default")
      (node (ref "IC15") (pin "22") (pinfunction "X9_22") (pintype "input"))
      (node (ref "X72") (pin "10") (pinfunction "S_10") (pintype "passive"))
    )
    (net (code "297") (name "Net-(IC15A-X10)") (class "Default")
      (node (ref "IC15") (pin "21") (pinfunction "X10_21") (pintype "input"))
      (node (ref "X72") (pin "9") (pinfunction "S_9") (pintype "passive"))
    )
    (net (code "298") (name "Net-(IC15A-X11)") (class "Default")
      (node (ref "IC15") (pin "20") (pinfunction "X11_20") (pintype "input"))
      (node (ref "X72") (pin "8") (pinfunction "S_8") (pintype "passive"))
    )
    (net (code "299") (name "Net-(IC15A-X12)") (class "Default")
      (node (ref "IC15") (pin "19") (pinfunction "X12_19") (pintype "input"))
      (node (ref "X72") (pin "7") (pinfunction "S_7") (pintype "passive"))
    )
    (net (code "300") (name "Net-(IC15A-X13)") (class "Default")
      (node (ref "IC15") (pin "18") (pinfunction "X13_18") (pintype "input"))
      (node (ref "X72") (pin "6") (pinfunction "S_6") (pintype "passive"))
    )
    (net (code "301") (name "Net-(IC15A-X14)") (class "Default")
      (node (ref "IC15") (pin "17") (pinfunction "X14_17") (pintype "input"))
      (node (ref "X72") (pin "5") (pinfunction "S_5") (pintype "passive"))
    )
    (net (code "302") (name "Net-(IC15A-X15)") (class "Default")
      (node (ref "IC15") (pin "16") (pinfunction "X15_16") (pintype "input"))
      (node (ref "X72") (pin "4") (pinfunction "S_4") (pintype "passive"))
    )
    (net (code "303") (name "Net-(IC15B-VDD)") (class "Default")
      (node (ref "IC15") (pin "24") (pinfunction "VDD_24") (pintype "power_in"))
      (node (ref "X72") (pin "12") (pinfunction "S_12") (pintype "passive"))
    )
    (net (code "304") (name "Net-(IC15B-VSS)") (class "Default")
      (node (ref "IC15") (pin "12") (pinfunction "VSS_12") (pintype "power_in"))
      (node (ref "X71") (pin "12") (pinfunction "S_12") (pintype "passive"))
    )
    (net (code "305") (name "Net-(IC16-CD+)") (class "Default")
      (node (ref "IC16") (pin "9") (pinfunction "CD+_9") (pintype "passive"))
      (node (ref "X74") (pin "1") (pinfunction "S_1") (pintype "passive"))
    )
    (net (code "306") (name "Net-(IC16-GND)") (class "Default")
      (node (ref "IC16") (pin "8") (pinfunction "GND_8") (pintype "power_in"))
      (node (ref "X73") (pin "8") (pinfunction "S_8") (pintype "passive"))
    )
    (net (code "307") (name "Net-(IC16-I1)") (class "Default")
      (node (ref "IC16") (pin "1") (pinfunction "I1_1") (pintype "input"))
      (node (ref "X73") (pin "1") (pinfunction "S_1") (pintype "passive"))
    )
    (net (code "308") (name "Net-(IC16-I2)") (class "Default")
      (node (ref "IC16") (pin "2") (pinfunction "I2_2") (pintype "input"))
      (node (ref "X73") (pin "2") (pinfunction "S_2") (pintype "passive"))
    )
    (net (code "309") (name "Net-(IC16-I3)") (class "Default")
      (node (ref "IC16") (pin "3") (pinfunction "I3_3") (pintype "input"))
      (node (ref "X73") (pin "3") (pinfunction "S_3") (pintype "passive"))
    )
    (net (code "310") (name "Net-(IC16-I4)") (class "Default")
      (node (ref "IC16") (pin "4") (pinfunction "I4_4") (pintype "input"))
      (node (ref "X73") (pin "4") (pinfunction "S_4") (pintype "passive"))
    )
    (net (code "311") (name "Net-(IC16-I5)") (class "Default")
      (node (ref "IC16") (pin "5") (pinfunction "I5_5") (pintype "input"))
      (node (ref "X73") (pin "5") (pinfunction "S_5") (pintype "passive"))
    )
    (net (code "312") (name "Net-(IC16-I6)") (class "Default")
      (node (ref "IC16") (pin "6") (pinfunction "I6_6") (pintype "input"))
      (node (ref "X73") (pin "6") (pinfunction "S_6") (pintype "passive"))
    )
    (net (code "313") (name "Net-(IC16-I7)") (class "Default")
      (node (ref "IC16") (pin "7") (pinfunction "I7_7") (pintype "input"))
      (node (ref "X73") (pin "7") (pinfunction "S_7") (pintype "passive"))
    )
    (net (code "314") (name "Net-(IC16-O1)") (class "Default")
      (node (ref "IC16") (pin "16") (pinfunction "O1_16") (pintype "open_collector"))
      (node (ref "X74") (pin "8") (pinfunction "S_8") (pintype "passive"))
    )
    (net (code "315") (name "Net-(IC16-O2)") (class "Default")
      (node (ref "IC16") (pin "15") (pinfunction "O2_15") (pintype "open_collector"))
      (node (ref "X74") (pin "7") (pinfunction "S_7") (pintype "passive"))
    )
    (net (code "316") (name "Net-(IC16-O3)") (class "Default")
      (node (ref "IC16") (pin "14") (pinfunction "O3_14") (pintype "open_collector"))
      (node (ref "X74") (pin "6") (pinfunction "S_6") (pintype "passive"))
    )
    (net (code "317") (name "Net-(IC16-O4)") (class "Default")
      (node (ref "IC16") (pin "13") (pinfunction "O4_13") (pintype "open_collector"))
      (node (ref "X74") (pin "5") (pinfunction "S_5") (pintype "passive"))
    )
    (net (code "318") (name "Net-(IC16-O5)") (class "Default")
      (node (ref "IC16") (pin "12") (pinfunction "O5_12") (pintype "open_collector"))
      (node (ref "X74") (pin "4") (pinfunction "S_4") (pintype "passive"))
    )
    (net (code "319") (name "Net-(IC16-O6)") (class "Default")
      (node (ref "IC16") (pin "11") (pinfunction "O6_11") (pintype "open_collector"))
      (node (ref "X74") (pin "3") (pinfunction "S_3") (pintype "passive"))
    )
    (net (code "320") (name "Net-(IC16-O7)") (class "Default")
      (node (ref "IC16") (pin "10") (pinfunction "O7_10") (pintype "open_collector"))
      (node (ref "X74") (pin "2") (pinfunction "S_2") (pintype "passive"))
    )
    (net (code "321") (name "Net-(Q1-B)") (class "Default")
      (node (ref "Q1") (pin "1") (pinfunction "B_1") (pintype "passive"))
      (node (ref "X5") (pin "1") (pinfunction "S_1") (pintype "passive"))
    )
    (net (code "322") (name "Net-(Q1-C)") (class "Default")
      (node (ref "Q1") (pin "2") (pinfunction "C_2") (pintype "passive"))
      (node (ref "X5") (pin "2") (pinfunction "S_2") (pintype "passive"))
    )
    (net (code "323") (name "Net-(Q1-E)") (class "Default")
      (node (ref "Q1") (pin "3") (pinfunction "E_3") (pintype "passive"))
      (node (ref "X5") (pin "3") (pinfunction "S_3") (pintype "passive"))
    )
    (net (code "324") (name "Net-(Q2-GND)") (class "Default")
      (node (ref "Q2") (pin "2") (pinfunction "GND_2") (pintype "passive"))
      (node (ref "X6") (pin "2") (pinfunction "S_2") (pintype "passive"))
    )
    (net (code "325") (name "Net-(Q2-IN)") (class "Default")
      (node (ref "Q2") (pin "3") (pinfunction "IN_3") (pintype "input"))
      (node (ref "X6") (pin "3") (pinfunction "S_3") (pintype "passive"))
    )
    (net (code "326") (name "Net-(Q2-OUT)") (class "Default")
      (node (ref "Q2") (pin "1") (pinfunction "OUT_1") (pintype "output"))
      (node (ref "X6") (pin "1") (pinfunction "S_1") (pintype "passive"))
    )
    (net (code "327") (name "Net-(Q2-V+)") (class "Default")
      (node (ref "Q2") (pin "4") (pinfunction "V+_4") (pintype "power_in"))
      (node (ref "X6") (pin "4") (pinfunction "S_4") (pintype "passive"))
    )
    (net (code "328") (name "Net-(Q4-B)") (class "Default")
      (node (ref "Q4") (pin "1") (pinfunction "B_1") (pintype "passive"))
      (node (ref "X8") (pin "1") (pinfunction "S_1") (pintype "passive"))
    )
    (net (code "329") (name "Net-(Q4-C)") (class "Default")
      (node (ref "Q4") (pin "2") (pinfunction "C_2") (pintype "passive"))
      (node (ref "X8") (pin "2") (pinfunction "S_2") (pintype "passive"))
    )
    (net (code "330") (name "Net-(Q4-E)") (class "Default")
      (node (ref "Q4") (pin "3") (pinfunction "E_3") (pintype "passive"))
      (node (ref "X8") (pin "3") (pinfunction "S_3") (pintype "passive"))
    )
    (net (code "331") (name "Net-(Q5-GND)") (class "Default")
      (node (ref "Q5") (pin "2") (pinfunction "GND_2") (pintype "passive"))
      (node (ref "X9") (pin "2") (pinfunction "S_2") (pintype "passive"))
    )
    (net (code "332") (name "Net-(Q5-IN)") (class "Default")
      (node (ref "Q5") (pin "3") (pinfunction "IN_3") (pintype "input"))
      (node (ref "X9") (pin "3") (pinfunction "S_3") (pintype "passive"))
    )
    (net (code "333") (name "Net-(Q5-OUT)") (class "Default")
      (node (ref "Q5") (pin "1") (pinfunction "OUT_1") (pintype "output"))
      (node (ref "X9") (pin "1") (pinfunction "S_1") (pintype "passive"))
    )
    (net (code "334") (name "Net-(Q5-V+)") (class "Default")
      (node (ref "Q5") (pin "4") (pinfunction "V+_4") (pintype "power_in"))
      (node (ref "X9") (pin "4") (pinfunction "S_4") (pintype "passive"))
    )
    (net (code "335") (name "Net-(Q7-B)") (class "Default")
      (node (ref "Q7") (pin "1") (pinfunction "B_1") (pintype "passive"))
      (node (ref "X15") (pin "1") (pinfunction "S_1") (pintype "passive"))
    )
    (net (code "336") (name "Net-(Q7-C)") (class "Default")
      (node (ref "Q7") (pin "2") (pinfunction "C_2") (pintype "passive"))
      (node (ref "X15") (pin "2") (pinfunction "S_2") (pintype "passive"))
    )
    (net (code "337") (name "Net-(Q7-E)") (class "Default")
      (node (ref "Q7") (pin "3") (pinfunction "E_3") (pintype "passive"))
      (node (ref "X15") (pin "3") (pinfunction "S_3") (pintype "passive"))
    )
    (net (code "338") (name "Net-(Q8-GND)") (class "Default")
      (node (ref "Q8") (pin "2") (pinfunction "GND_2") (pintype "passive"))
      (node (ref "X16") (pin "2") (pinfunction "S_2") (pintype "passive"))
    )
    (net (code "339") (name "Net-(Q8-IN)") (class "Default")
      (node (ref "Q8") (pin "3") (pinfunction "IN_3") (pintype "input"))
      (node (ref "X16") (pin "3") (pinfunction "S_3") (pintype "passive"))
    )
    (net (code "340") (name "Net-(Q8-OUT)") (class "Default")
      (node (ref "Q8") (pin "1") (pinfunction "OUT_1") (pintype "output"))
      (node (ref "X16") (pin "1") (pinfunction "S_1") (pintype "passive"))
    )
    (net (code "341") (name "Net-(Q8-V+)") (class "Default")
      (node (ref "Q8") (pin "4") (pinfunction "V+_4") (pintype "power_in"))
      (node (ref "X16") (pin "4") (pinfunction "S_4") (pintype "passive"))
    )
    (net (code "342") (name "Net-(Q10-B)") (class "Default")
      (node (ref "Q10") (pin "1") (pinfunction "B_1") (pintype "passive"))
      (node (ref "X18") (pin "1") (pinfunction "S_1") (pintype "passive"))
    )
    (net (code "343") (name "Net-(Q10-C)") (class "Default")
      (node (ref "Q10") (pin "2") (pinfunction "C_2") (pintype "passive"))
      (node (ref "X18") (pin "2") (pinfunction "S_2") (pintype "passive"))
    )
    (net (code "344") (name "Net-(Q10-E)") (class "Default")
      (node (ref "Q10") (pin "3") (pinfunction "E_3") (pintype "passive"))
      (node (ref "X18") (pin "3") (pinfunction "S_3") (pintype "passive"))
    )
    (net (code "345") (name "Net-(Q11-GND)") (class "Default")
      (node (ref "Q11") (pin "2") (pinfunction "GND_2") (pintype "passive"))
      (node (ref "X19") (pin "2") (pinfunction "S_2") (pintype "passive"))
    )
    (net (code "346") (name "Net-(Q11-IN)") (class "Default")
      (node (ref "Q11") (pin "3") (pinfunction "IN_3") (pintype "input"))
      (node (ref "X19") (pin "3") (pinfunction "S_3") (pintype "passive"))
    )
    (net (code "347") (name "Net-(Q11-OUT)") (class "Default")
      (node (ref "Q11") (pin "1") (pinfunction "OUT_1") (pintype "output"))
      (node (ref "X19") (pin "1") (pinfunction "S_1") (pintype "passive"))
    )
    (net (code "348") (name "Net-(Q11-V+)") (class "Default")
      (node (ref "Q11") (pin "4") (pinfunction "V+_4") (pintype "power_in"))
      (node (ref "X19") (pin "4") (pinfunction "S_4") (pintype "passive"))
    )
    (net (code "349") (name "Net-(Q13-B)") (class "Default")
      (node (ref "Q13") (pin "1") (pinfunction "B_1") (pintype "passive"))
      (node (ref "X25") (pin "1") (pinfunction "S_1") (pintype "passive"))
    )
    (net (code "350") (name "Net-(Q13-C)") (class "Default")
      (node (ref "Q13") (pin "2") (pinfunction "C_2") (pintype "passive"))
      (node (ref "X25") (pin "2") (pinfunction "S_2") (pintype "passive"))
    )
    (net (code "351") (name "Net-(Q13-E)") (class "Default")
      (node (ref "Q13") (pin "3") (pinfunction "E_3") (pintype "passive"))
      (node (ref "X25") (pin "3") (pinfunction "S_3") (pintype "passive"))
    )
    (net (code "352") (name "Net-(Q14-GND)") (class "Default")
      (node (ref "Q14") (pin "2") (pinfunction "GND_2") (pintype "passive"))
      (node (ref "X26") (pin "2") (pinfunction "S_2") (pintype "passive"))
    )
    (net (code "353") (name "Net-(Q14-IN)") (class "Default")
      (node (ref "Q14") (pin "3") (pinfunction "IN_3") (pintype "input"))
      (node (ref "X26") (pin "3") (pinfunction "S_3") (pintype "passive"))
    )
    (net (code "354") (name "Net-(Q14-OUT)") (class "Default")
      (node (ref "Q14") (pin "1") (pinfunction "OUT_1") (pintype "output"))
      (node (ref "X26") (pin "1") (pinfunction "S_1") (pintype "passive"))
    )
    (net (code "355") (name "Net-(Q14-V+)") (class "Default")
      (node (ref "Q14") (pin "4") (pinfunction "V+_4") (pintype "power_in"))
      (node (ref "X26") (pin "4") (pinfunction "S_4") (pintype "passive"))
    )
    (net (code "356") (name "Net-(Q16-B)") (class "Default")
      (node (ref "Q16") (pin "1") (pinfunction "B_1") (pintype "passive"))
      (node (ref "X28") (pin "1") (pinfunction "S_1") (pintype "passive"))
    )
    (net (code "357") (name "Net-(Q16-C)") (class "Default")
      (node (ref "Q16") (pin "2") (pinfunction "C_2") (pintype "passive"))
      (node (ref "X28") (pin "2") (pinfunction "S_2") (pintype "passive"))
    )
    (net (code "358") (name "Net-(Q16-E)") (class "Default")
      (node (ref "Q16") (pin "3") (pinfunction "E_3") (pintype "passive"))
      (node (ref "X28") (pin "3") (pinfunction "S_3") (pintype "passive"))
    )
    (net (code "359") (name "Net-(Q17-GND)") (class "Default")
      (node (ref "Q17") (pin "2") (pinfunction "GND_2") (pintype "passive"))
      (node (ref "X29") (pin "2") (pinfunction "S_2") (pintype "passive"))
    )
    (net (code "360") (name "Net-(Q17-IN)") (class "Default")
      (node (ref "Q17") (pin "3") (pinfunction "IN_3") (pintype "input"))
      (node (ref "X29") (pin "3") (pinfunction "S_3") (pintype "passive"))
    )
    (net (code "361") (name "Net-(Q17-OUT)") (class "Default")
      (node (ref "Q17") (pin "1") (pinfunction "OUT_1") (pintype "output"))
      (node (ref "X29") (pin "1") (pinfunction "S_1") (pintype "passive"))
    )
    (net (code "362") (name "Net-(Q17-V+)") (class "Default")
      (node (ref "Q17") (pin "4") (pinfunction "V+_4") (pintype "power_in"))
      (node (ref "X29") (pin "4") (pinfunction "S_4") (pintype "passive"))
    )
    (net (code "363") (name "Net-(Q19-B)") (class "Default")
      (node (ref "Q19") (pin "1") (pinfunction "B_1") (pintype "passive"))
      (node (ref "X35") (pin "1") (pinfunction "S_1") (pintype "passive"))
    )
    (net (code "364") (name "Net-(Q19-C)") (class "Default")
      (node (ref "Q19") (pin "2") (pinfunction "C_2") (pintype "passive"))
      (node (ref "X35") (pin "2") (pinfunction "S_2") (pintype "passive"))
    )
    (net (code "365") (name "Net-(Q19-E)") (class "Default")
      (node (ref "Q19") (pin "3") (pinfunction "E_3") (pintype "passive"))
      (node (ref "X35") (pin "3") (pinfunction "S_3") (pintype "passive"))
    )
    (net (code "366") (name "Net-(Q20-GND)") (class "Default")
      (node (ref "Q20") (pin "2") (pinfunction "GND_2") (pintype "passive"))
      (node (ref "X36") (pin "2") (pinfunction "S_2") (pintype "passive"))
    )
    (net (code "367") (name "Net-(Q20-IN)") (class "Default")
      (node (ref "Q20") (pin "3") (pinfunction "IN_3") (pintype "input"))
      (node (ref "X36") (pin "3") (pinfunction "S_3") (pintype "passive"))
    )
    (net (code "368") (name "Net-(Q20-OUT)") (class "Default")
      (node (ref "Q20") (pin "1") (pinfunction "OUT_1") (pintype "output"))
      (node (ref "X36") (pin "1") (pinfunction "S_1") (pintype "passive"))
    )
    (net (code "369") (name "Net-(Q20-V+)") (class "Default")
      (node (ref "Q20") (pin "4") (pinfunction "V+_4") (pintype "power_in"))
      (node (ref "X36") (pin "4") (pinfunction "S_4") (pintype "passive"))
    )
    (net (code "370") (name "Net-(Q22-B)") (class "Default")
      (node (ref "Q22") (pin "1") (pinfunction "B_1") (pintype "passive"))
      (node (ref "X38") (pin "1") (pinfunction "S_1") (pintype "passive"))
    )
    (net (code "371") (name "Net-(Q22-C)") (class "Default")
      (node (ref "Q22") (pin "2") (pinfunction "C_2") (pintype "passive"))
      (node (ref "X38") (pin "2") (pinfunction "S_2") (pintype "passive"))
    )
    (net (code "372") (name "Net-(Q22-E)") (class "Default")
      (node (ref "Q22") (pin "3") (pinfunction "E_3") (pintype "passive"))
      (node (ref "X38") (pin "3") (pinfunction "S_3") (pintype "passive"))
    )
    (net (code "373") (name "Net-(Q23-GND)") (class "Default")
      (node (ref "Q23") (pin "2") (pinfunction "GND_2") (pintype "passive"))
      (node (ref "X39") (pin "2") (pinfunction "S_2") (pintype "passive"))
    )
    (net (code "374") (name "Net-(Q23-IN)") (class "Default")
      (node (ref "Q23") (pin "3") (pinfunction "IN_3") (pintype "input"))
      (node (ref "X39") (pin "3") (pinfunction "S_3") (pintype "passive"))
    )
    (net (code "375") (name "Net-(Q23-OUT)") (class "Default")
      (node (ref "Q23") (pin "1") (pinfunction "OUT_1") (pintype "output"))
      (node (ref "X39") (pin "1") (pinfunction "S_1") (pintype "passive"))
    )
    (net (code "376") (name "Net-(Q23-V+)") (class "Default")
      (node (ref "Q23") (pin "4") (pinfunction "V+_4") (pintype "power_in"))
      (node (ref "X39") (pin "4") (pinfunction "S_4") (pintype "passive"))
    )
    (net (code "377") (name "Net-(Q25-B)") (class "Default")
      (node (ref "Q25") (pin "1") (pinfunction "B_1") (pintype "passive"))
      (node (ref "X45") (pin "1") (pinfunction "S_1") (pintype "passive"))
    )
    (net (code "378") (name "Net-(Q25-C)") (class "Default")
      (node (ref "Q25") (pin "2") (pinfunction "C_2") (pintype "passive"))
      (node (ref "X45") (pin "2") (pinfunction "S_2") (pintype "passive"))
    )
    (net (code "379") (name "Net-(Q25-E)") (class "Default")
      (node (ref "Q25") (pin "3") (pinfunction "E_3") (pintype "passive"))
      (node (ref "X45") (pin "3") (pinfunction "S_3") (pintype "passive"))
    )
    (net (code "380") (name "Net-(Q26-GND)") (class "Default")
      (node (ref "Q26") (pin "2") (pinfunction "GND_2") (pintype "passive"))
      (node (ref "X46") (pin "2") (pinfunction "S_2") (pintype "passive"))
    )
    (net (code "381") (name "Net-(Q26-IN)") (class "Default")
      (node (ref "Q26") (pin "3") (pinfunction "IN_3") (pintype "input"))
      (node (ref "X46") (pin "3") (pinfunction "S_3") (pintype "passive"))
    )
    (net (code "382") (name "Net-(Q26-OUT)") (class "Default")
      (node (ref "Q26") (pin "1") (pinfunction "OUT_1") (pintype "output"))
      (node (ref "X46") (pin "1") (pinfunction "S_1") (pintype "passive"))
    )
    (net (code "383") (name "Net-(Q26-V+)") (class "Default")
      (node (ref "Q26") (pin "4") (pinfunction "V+_4") (pintype "power_in"))
      (node (ref "X46") (pin "4") (pinfunction "S_4") (pintype "passive"))
    )
    (net (code "384") (name "Net-(Q28-B)") (class "Default")
      (node (ref "Q28") (pin "1") (pinfunction "B_1") (pintype "passive"))
      (node (ref "X48") (pin "1") (pinfunction "S_1") (pintype "passive"))
    )
    (net (code "385") (name "Net-(Q28-C)") (class "Default")
      (node (ref "Q28") (pin "2") (pinfunction "C_2") (pintype "passive"))
      (node (ref "X48") (pin "2") (pinfunction "S_2") (pintype "passive"))
    )
    (net (code "386") (name "Net-(Q28-E)") (class "Default")
      (node (ref "Q28") (pin "3") (pinfunction "E_3") (pintype "passive"))
      (node (ref "X48") (pin "3") (pinfunction "S_3") (pintype "passive"))
    )
    (net (code "387") (name "Net-(Q29-GND)") (class "Default")
      (node (ref "Q29") (pin "2") (pinfunction "GND_2") (pintype "passive"))
      (node (ref "X49") (pin "2") (pinfunction "S_2") (pintype "passive"))
    )
    (net (code "388") (name "Net-(Q29-IN)") (class "Default")
      (node (ref "Q29") (pin "3") (pinfunction "IN_3") (pintype "input"))
      (node (ref "X49") (pin "3") (pinfunction "S_3") (pintype "passive"))
    )
    (net (code "389") (name "Net-(Q29-OUT)") (class "Default")
      (node (ref "Q29") (pin "1") (pinfunction "OUT_1") (pintype "output"))
      (node (ref "X49") (pin "1") (pinfunction "S_1") (pintype "passive"))
    )
    (net (code "390") (name "Net-(Q29-V+)") (class "Default")
      (node (ref "Q29") (pin "4") (pinfunction "V+_4") (pintype "power_in"))
      (node (ref "X49") (pin "4") (pinfunction "S_4") (pintype "passive"))
    )
    (net (code "391") (name "Net-(Q31-B)") (class "Default")
      (node (ref "Q31") (pin "1") (pinfunction "B_1") (pintype "passive"))
      (node (ref "X55") (pin "1") (pinfunction "S_1") (pintype "passive"))
    )
    (net (code "392") (name "Net-(Q31-C)") (class "Default")
      (node (ref "Q31") (pin "2") (pinfunction "C_2") (pintype "passive"))
      (node (ref "X55") (pin "2") (pinfunction "S_2") (pintype "passive"))
    )
    (net (code "393") (name "Net-(Q31-E)") (class "Default")
      (node (ref "Q31") (pin "3") (pinfunction "E_3") (pintype "passive"))
      (node (ref "X55") (pin "3") (pinfunction "S_3") (pintype "passive"))
    )
    (net (code "394") (name "Net-(Q32-GND)") (class "Default")
      (node (ref "Q32") (pin "2") (pinfunction "GND_2") (pintype "passive"))
      (node (ref "X56") (pin "2") (pinfunction "S_2") (pintype "passive"))
    )
    (net (code "395") (name "Net-(Q32-IN)") (class "Default")
      (node (ref "Q32") (pin "3") (pinfunction "IN_3") (pintype "input"))
      (node (ref "X56") (pin "3") (pinfunction "S_3") (pintype "passive"))
    )
    (net (code "396") (name "Net-(Q32-OUT)") (class "Default")
      (node (ref "Q32") (pin "1") (pinfunction "OUT_1") (pintype "output"))
      (node (ref "X56") (pin "1") (pinfunction "S_1") (pintype "passive"))
    )
    (net (code "397") (name "Net-(Q32-V+)") (class "Default")
      (node (ref "Q32") (pin "4") (pinfunction "V+_4") (pintype "power_in"))
      (node (ref "X56") (pin "4") (pinfunction "S_4") (pintype "passive"))
    )
    (net (code "398") (name "Net-(Q34-B)") (class "Default")
      (node (ref "Q34") (pin "1") (pinfunction "B_1") (pintype "passive"))
      (node (ref "X58") (pin "1") (pinfunction "S_1") (pintype "passive"))
    )
    (net (code "399") (name "Net-(Q34-C)") (class "Default")
      (node (ref "Q34") (pin "2") (pinfunction "C_2") (pintype "passive"))
      (node (ref "X58") (pin "2") (pinfunction "S_2") (pintype "passive"))
    )
    (net (code "400") (name "Net-(Q34-E)") (class "Default")
      (node (ref "Q34") (pin "3") (pinfunction "E_3") (pintype "passive"))
      (node (ref "X58") (pin "3") (pinfunction "S_3") (pintype "passive"))
    )
    (net (code "401") (name "Net-(Q35-GND)") (class "Default")
      (node (ref "Q35") (pin "2") (pinfunction "GND_2") (pintype "passive"))
      (node (ref "X59") (pin "2") (pinfunction "S_2") (pintype "passive"))
    )
    (net (code "402") (name "Net-(Q35-IN)") (class "Default")
      (node (ref "Q35") (pin "3") (pinfunction "IN_3") (pintype "input"))
      (node (ref "X59") (pin "3") (pinfunction "S_3") (pintype "passive"))
    )
    (net (code "403") (name "Net-(Q35-OUT)") (class "Default")
      (node (ref "Q35") (pin "1") (pinfunction "OUT_1") (pintype "output"))
      (node (ref "X59") (pin "1") (pinfunction "S_1") (pintype "passive"))
    )
    (net (code "404") (name "Net-(Q35-V+)") (class "Default")
      (node (ref "Q35") (pin "4") (pinfunction "V+_4") (pintype "power_in"))
      (node (ref "X59") (pin "4") (pinfunction "S_4") (pintype "passive"))
    )
    (net (code "405") (name "Net-(Q37-B)") (class "Default")
      (node (ref "Q37") (pin "1") (pinfunction "B_1") (pintype "passive"))
      (node (ref "X65") (pin "1") (pinfunction "S_1") (pintype "passive"))
    )
    (net (code "406") (name "Net-(Q37-C)") (class "Default")
      (node (ref "Q37") (pin "2") (pinfunction "C_2") (pintype "passive"))
      (node (ref "X65") (pin "2") (pinfunction "S_2") (pintype "passive"))
    )
    (net (code "407") (name "Net-(Q37-E)") (class "Default")
      (node (ref "Q37") (pin "3") (pinfunction "E_3") (pintype "passive"))
      (node (ref "X65") (pin "3") (pinfunction "S_3") (pintype "passive"))
    )
    (net (code "408") (name "Net-(Q38-GND)") (class "Default")
      (node (ref "Q38") (pin "2") (pinfunction "GND_2") (pintype "passive"))
      (node (ref "X66") (pin "2") (pinfunction "S_2") (pintype "passive"))
    )
    (net (code "409") (name "Net-(Q38-IN)") (class "Default")
      (node (ref "Q38") (pin "3") (pinfunction "IN_3") (pintype "input"))
      (node (ref "X66") (pin "3") (pinfunction "S_3") (pintype "passive"))
    )
    (net (code "410") (name "Net-(Q38-OUT)") (class "Default")
      (node (ref "Q38") (pin "1") (pinfunction "OUT_1") (pintype "output"))
      (node (ref "X66") (pin "1") (pinfunction "S_1") (pintype "passive"))
    )
    (net (code "411") (name "Net-(Q38-V+)") (class "Default")
      (node (ref "Q38") (pin "4") (pinfunction "V+_4") (pintype "power_in"))
      (node (ref "X66") (pin "4") (pinfunction "S_4") (pintype "passive"))
    )
    (net (code "412") (name "Net-(Q40-B)") (class "Default")
      (node (ref "Q40") (pin "1") (pinfunction "B_1") (pintype "passive"))
      (node (ref "X68") (pin "1") (pinfunction "S_1") (pintype "passive"))
    )
    (net (code "413") (name "Net-(Q40-C)") (class "Default")
      (node (ref "Q40") (pin "2") (pinfunction "C_2") (pintype "passive"))
      (node (ref "X68") (pin "2") (pinfunction "S_2") (pintype "passive"))
    )
    (net (code "414") (name "Net-(Q40-E)") (class "Default")
      (node (ref "Q40") (pin "3") (pinfunction "E_3") (pintype "passive"))
      (node (ref "X68") (pin "3") (pinfunction "S_3") (pintype "passive"))
    )
    (net (code "415") (name "Net-(Q41-GND)") (class "Default")
      (node (ref "Q41") (pin "2") (pinfunction "GND_2") (pintype "passive"))
      (node (ref "X69") (pin "2") (pinfunction "S_2") (pintype "passive"))
    )
    (net (code "416") (name "Net-(Q41-IN)") (class "Default")
      (node (ref "Q41") (pin "3") (pinfunction "IN_3") (pintype "input"))
      (node (ref "X69") (pin "3") (pinfunction "S_3") (pintype "passive"))
    )
    (net (code "417") (name "Net-(Q41-OUT)") (class "Default")
      (node (ref "Q41") (pin "1") (pinfunction "OUT_1") (pintype "output"))
      (node (ref "X69") (pin "1") (pinfunction "S_1") (pintype "passive"))
    )
    (net (code "418") (name "Net-(Q41-V+)") (class "Default")
      (node (ref "Q41") (pin "4") (pinfunction "V+_4") (pintype "power_in"))
      (node (ref "X69") (pin "4") (pinfunction "S_4") (pintype "passive"))
    )
    (net (code "419") (name "Net-(Q43-B)") (class "Default")
      (node (ref "Q43") (pin "1") (pinfunction "B_1") (pintype "passive"))
      (node (ref "X75") (pin "1") (pinfunction "S_1") (pintype "passive"))
    )
    (net (code "420") (name "Net-(Q43-C)") (class "Default")
      (node (ref "Q43") (pin "2") (pinfunction "C_2") (pintype "passive"))
      (node (ref "X75") (pin "2") (pinfunction "S_2") (pintype "passive"))
    )
    (net (code "421") (name "Net-(Q43-E)") (class "Default")
      (node (ref "Q43") (pin "3") (pinfunction "E_3") (pintype "passive"))
      (node (ref "X75") (pin "3") (pinfunction "S_3") (pintype "passive"))
    )
    (net (code "422") (name "Net-(Q44-GND)") (class "Default")
      (node (ref "Q44") (pin "2") (pinfunction "GND_2") (pintype "passive"))
      (node (ref "X76") (pin "2") (pinfunction "S_2") (pintype "passive"))
    )
    (net (code "423") (name "Net-(Q44-IN)") (class "Default")
      (node (ref "Q44") (pin "3") (pinfunction "IN_3") (pintype "input"))
      (node (ref "X76") (pin "3") (pinfunction "S_3") (pintype "passive"))
    )
    (net (code "424") (name "Net-(Q44-OUT)") (class "Default")
      (node (ref "Q44") (pin "1") (pinfunction "OUT_1") (pintype "output"))
      (node (ref "X76") (pin "1") (pinfunction "S_1") (pintype "passive"))
    )
    (net (code "425") (name "Net-(Q44-V+)") (class "Default")
      (node (ref "Q44") (pin "4") (pinfunction "V+_4") (pintype "power_in"))
      (node (ref "X76") (pin "4") (pinfunction "S_4") (pintype "passive"))
    )
    (net (code "426") (name "Net-(Q46-B)") (class "Default")
      (node (ref "Q46") (pin "1") (pinfunction "B_1") (pintype "passive"))
      (node (ref "X78") (pin "1") (pinfunction "S_1") (pintype "passive"))
    )
    (net (code "427") (name "Net-(Q46-C)") (class "Default")
      (node (ref "Q46") (pin "2") (pinfunction "C_2") (pintype "passive"))
      (node (ref "X78") (pin "2") (pinfunction "S_2") (pintype "passive"))
    )
    (net (code "428") (name "Net-(Q46-E)") (class "Default")
      (node (ref "Q46") (pin "3") (pinfunction "E_3") (pintype "passive"))
      (node (ref "X78") (pin "3") (pinfunction "S_3") (pintype "passive"))
    )
    (net (code "429") (name "Net-(Q47-GND)") (class "Default")
      (node (ref "Q47") (pin "2") (pinfunction "GND_2") (pintype "passive"))
      (node (ref "X79") (pin "2") (pinfunction "S_2") (pintype "passive"))
    )
    (net (code "430") (name "Net-(Q47-IN)") (class "Default")
      (node (ref "Q47") (pin "3") (pinfunction "IN_3") (pintype "input"))
      (node (ref "X79") (pin "3") (pinfunction "S_3") (pintype "passive"))
    )
    (net (code "431") (name "Net-(Q47-OUT)") (class "Default")
      (node (ref "Q47") (pin "1") (pinfunction "OUT_1") (pintype "output"))
      (node (ref "X79") (pin "1") (pinfunction "S_1") (pintype "passive"))
    )
    (net (code "432") (name "Net-(Q47-V+)") (class "Default")
      (node (ref "Q47") (pin "4") (pinfunction "V+_4") (pintype "power_in"))
      (node (ref "X79") (pin "4") (pinfunction "S_4") (pintype "passive"))
    )
    (net (code "433") (name "Net-(X7A-S)") (class "Default")
      (node (ref "Q3") (pin "B") (pinfunction "B_B") (pintype "passive"))
      (node (ref "X7") (pin "1") (pinfunction "S_1") (pintype "passive"))
    )
    (net (code "434") (name "Net-(X7B-S)") (class "Default")
      (node (ref "Q3") (pin "E") (pinfunction "E_E") (pintype "passive"))
      (node (ref "X7") (pin "2") (pinfunction "S_2") (pintype "passive"))
    )
    (net (code "435") (name "Net-(X7C-S)") (class "Default")
      (node (ref "Q3") (pin "C") (pinfunction "C_C") (pintype "passive"))
      (node (ref "X7") (pin "3") (pinfunction "S_3") (pintype "passive"))
    )
    (net (code "436") (name "Net-(X10A-S)") (class "Default")
      (node (ref "Q6") (pin "B") (pinfunction "B_B") (pintype "passive"))
      (node (ref "X10") (pin "1") (pinfunction "S_1") (pintype "passive"))
    )
    (net (code "437") (name "Net-(X10B-S)") (class "Default")
      (node (ref "Q6") (pin "E") (pinfunction "E_E") (pintype "passive"))
      (node (ref "X10") (pin "2") (pinfunction "S_2") (pintype "passive"))
    )
    (net (code "438") (name "Net-(X10C-S)") (class "Default")
      (node (ref "Q6") (pin "C") (pinfunction "C_C") (pintype "passive"))
      (node (ref "X10") (pin "3") (pinfunction "S_3") (pintype "passive"))
    )
    (net (code "439") (name "Net-(X17A-S)") (class "Default")
      (node (ref "Q9") (pin "B") (pinfunction "B_B") (pintype "passive"))
      (node (ref "X17") (pin "1") (pinfunction "S_1") (pintype "passive"))
    )
    (net (code "440") (name "Net-(X17B-S)") (class "Default")
      (node (ref "Q9") (pin "E") (pinfunction "E_E") (pintype "passive"))
      (node (ref "X17") (pin "2") (pinfunction "S_2") (pintype "passive"))
    )
    (net (code "441") (name "Net-(X17C-S)") (class "Default")
      (node (ref "Q9") (pin "C") (pinfunction "C_C") (pintype "passive"))
      (node (ref "X17") (pin "3") (pinfunction "S_3") (pintype "passive"))
    )
    (net (code "442") (name "Net-(X20A-S)") (class "Default")
      (node (ref "Q12") (pin "B") (pinfunction "B_B") (pintype "passive"))
      (node (ref "X20") (pin "1") (pinfunction "S_1") (pintype "passive"))
    )
    (net (code "443") (name "Net-(X20B-S)") (class "Default")
      (node (ref "Q12") (pin "E") (pinfunction "E_E") (pintype "passive"))
      (node (ref "X20") (pin "2") (pinfunction "S_2") (pintype "passive"))
    )
    (net (code "444") (name "Net-(X20C-S)") (class "Default")
      (node (ref "Q12") (pin "C") (pinfunction "C_C") (pintype "passive"))
      (node (ref "X20") (pin "3") (pinfunction "S_3") (pintype "passive"))
    )
    (net (code "445") (name "Net-(X27A-S)") (class "Default")
      (node (ref "Q15") (pin "B") (pinfunction "B_B") (pintype "passive"))
      (node (ref "X27") (pin "1") (pinfunction "S_1") (pintype "passive"))
    )
    (net (code "446") (name "Net-(X27B-S)") (class "Default")
      (node (ref "Q15") (pin "E") (pinfunction "E_E") (pintype "passive"))
      (node (ref "X27") (pin "2") (pinfunction "S_2") (pintype "passive"))
    )
    (net (code "447") (name "Net-(X27C-S)") (class "Default")
      (node (ref "Q15") (pin "C") (pinfunction "C_C") (pintype "passive"))
      (node (ref "X27") (pin "3") (pinfunction "S_3") (pintype "passive"))
    )
    (net (code "448") (name "Net-(X30A-S)") (class "Default")
      (node (ref "Q18") (pin "B") (pinfunction "B_B") (pintype "passive"))
      (node (ref "X30") (pin "1") (pinfunction "S_1") (pintype "passive"))
    )
    (net (code "449") (name "Net-(X30B-S)") (class "Default")
      (node (ref "Q18") (pin "E") (pinfunction "E_E") (pintype "passive"))
      (node (ref "X30") (pin "2") (pinfunction "S_2") (pintype "passive"))
    )
    (net (code "450") (name "Net-(X30C-S)") (class "Default")
      (node (ref "Q18") (pin "C") (pinfunction "C_C") (pintype "passive"))
      (node (ref "X30") (pin "3") (pinfunction "S_3") (pintype "passive"))
    )
    (net (code "451") (name "Net-(X37A-S)") (class "Default")
      (node (ref "Q21") (pin "B") (pinfunction "B_B") (pintype "passive"))
      (node (ref "X37") (pin "1") (pinfunction "S_1") (pintype "passive"))
    )
    (net (code "452") (name "Net-(X37B-S)") (class "Default")
      (node (ref "Q21") (pin "E") (pinfunction "E_E") (pintype "passive"))
      (node (ref "X37") (pin "2") (pinfunction "S_2") (pintype "passive"))
    )
    (net (code "453") (name "Net-(X37C-S)") (class "Default")
      (node (ref "Q21") (pin "C") (pinfunction "C_C") (pintype "passive"))
      (node (ref "X37") (pin "3") (pinfunction "S_3") (pintype "passive"))
    )
    (net (code "454") (name "Net-(X40A-S)") (class "Default")
      (node (ref "Q24") (pin "B") (pinfunction "B_B") (pintype "passive"))
      (node (ref "X40") (pin "1") (pinfunction "S_1") (pintype "passive"))
    )
    (net (code "455") (name "Net-(X40B-S)") (class "Default")
      (node (ref "Q24") (pin "E") (pinfunction "E_E") (pintype "passive"))
      (node (ref "X40") (pin "2") (pinfunction "S_2") (pintype "passive"))
    )
    (net (code "456") (name "Net-(X40C-S)") (class "Default")
      (node (ref "Q24") (pin "C") (pinfunction "C_C") (pintype "passive"))
      (node (ref "X40") (pin "3") (pinfunction "S_3") (pintype "passive"))
    )
    (net (code "457") (name "Net-(X47A-S)") (class "Default")
      (node (ref "Q27") (pin "B") (pinfunction "B_B") (pintype "passive"))
      (node (ref "X47") (pin "1") (pinfunction "S_1") (pintype "passive"))
    )
    (net (code "458") (name "Net-(X47B-S)") (class "Default")
      (node (ref "Q27") (pin "E") (pinfunction "E_E") (pintype "passive"))
      (node (ref "X47") (pin "2") (pinfunction "S_2") (pintype "passive"))
    )
    (net (code "459") (name "Net-(X47C-S)") (class "Default")
      (node (ref "Q27") (pin "C") (pinfunction "C_C") (pintype "passive"))
      (node (ref "X47") (pin "3") (pinfunction "S_3") (pintype "passive"))
    )
    (net (code "460") (name "Net-(X50A-S)") (class "Default")
      (node (ref "Q30") (pin "B") (pinfunction "B_B") (pintype "passive"))
      (node (ref "X50") (pin "1") (pinfunction "S_1") (pintype "passive"))
    )
    (net (code "461") (name "Net-(X50B-S)") (class "Default")
      (node (ref "Q30") (pin "E") (pinfunction "E_E") (pintype "passive"))
      (node (ref "X50") (pin "2") (pinfunction "S_2") (pintype "passive"))
    )
    (net (code "462") (name "Net-(X50C-S)") (class "Default")
      (node (ref "Q30") (pin "C") (pinfunction "C_C") (pintype "passive"))
      (node (ref "X50") (pin "3") (pinfunction "S_3") (pintype "passive"))
    )
    (net (code "463") (name "Net-(X57A-S)") (class "Default")
      (node (ref "Q33") (pin "B") (pinfunction "B_B") (pintype "passive"))
      (node (ref "X57") (pin "1") (pinfunction "S_1") (pintype "passive"))
    )
    (net (code "464") (name "Net-(X57B-S)") (class "Default")
      (node (ref "Q33") (pin "E") (pinfunction "E_E") (pintype "passive"))
      (node (ref "X57") (pin "2") (pinfunction "S_2") (pintype "passive"))
    )
    (net (code "465") (name "Net-(X57C-S)") (class "Default")
      (node (ref "Q33") (pin "C") (pinfunction "C_C") (pintype "passive"))
      (node (ref "X57") (pin "3") (pinfunction "S_3") (pintype "passive"))
    )
    (net (code "466") (name "Net-(X60A-S)") (class "Default")
      (node (ref "Q36") (pin "B") (pinfunction "B_B") (pintype "passive"))
      (node (ref "X60") (pin "1") (pinfunction "S_1") (pintype "passive"))
    )
    (net (code "467") (name "Net-(X60B-S)") (class "Default")
      (node (ref "Q36") (pin "E") (pinfunction "E_E") (pintype "passive"))
      (node (ref "X60") (pin "2") (pinfunction "S_2") (pintype "passive"))
    )
    (net (code "468") (name "Net-(X60C-S)") (class "Default")
      (node (ref "Q36") (pin "C") (pinfunction "C_C") (pintype "passive"))
      (node (ref "X60") (pin "3") (pinfunction "S_3") (pintype "passive"))
    )
    (net (code "469") (name "Net-(X67A-S)") (class "Default")
      (node (ref "Q39") (pin "B") (pinfunction "B_B") (pintype "passive"))
      (node (ref "X67") (pin "1") (pinfunction "S_1") (pintype "passive"))
    )
    (net (code "470") (name "Net-(X67B-S)") (class "Default")
      (node (ref "Q39") (pin "E") (pinfunction "E_E") (pintype "passive"))
      (node (ref "X67") (pin "2") (pinfunction "S_2") (pintype "passive"))
    )
    (net (code "471") (name "Net-(X67C-S)") (class "Default")
      (node (ref "Q39") (pin "C") (pinfunction "C_C") (pintype "passive"))
      (node (ref "X67") (pin "3") (pinfunction "S_3") (pintype "passive"))
    )
    (net (code "472") (name "Net-(X70A-S)") (class "Default")
      (node (ref "Q42") (pin "B") (pinfunction "B_B") (pintype "passive"))
      (node (ref "X70") (pin "1") (pinfunction "S_1") (pintype "passive"))
    )
    (net (code "473") (name "Net-(X70B-S)") (class "Default")
      (node (ref "Q42") (pin "E") (pinfunction "E_E") (pintype "passive"))
      (node (ref "X70") (pin "2") (pinfunction "S_2") (pintype "passive"))
    )
    (net (code "474") (name "Net-(X70C-S)") (class "Default")
      (node (ref "Q42") (pin "C") (pinfunction "C_C") (pintype "passive"))
      (node (ref "X70") (pin "3") (pinfunction "S_3") (pintype "passive"))
    )
    (net (code "475") (name "Net-(X77A-S)") (class "Default")
      (node (ref "Q45") (pin "B") (pinfunction "B_B") (pintype "passive"))
      (node (ref "X77") (pin "1") (pinfunction "S_1") (pintype "passive"))
    )
    (net (code "476") (name "Net-(X77B-S)") (class "Default")
      (node (ref "Q45") (pin "E") (pinfunction "E_E") (pintype "passive"))
      (node (ref "X77") (pin "2") (pinfunction "S_2") (pintype "passive"))
    )
    (net (code "477") (name "Net-(X77C-S)") (class "Default")
      (node (ref "Q45") (pin "C") (pinfunction "C_C") (pintype "passive"))
      (node (ref "X77") (pin "3") (pinfunction "S_3") (pintype "passive"))
    )
    (net (code "478") (name "Net-(X80A-S)") (class "Default")
      (node (ref "Q48") (pin "B") (pinfunction "B_B") (pintype "passive"))
      (node (ref "X80") (pin "1") (pinfunction "S_1") (pintype "passive"))
    )
    (net (code "479") (name "Net-(X80B-S)") (class "Default")
      (node (ref "Q48") (pin "E") (pinfunction "E_E") (pintype "passive"))
      (node (ref "X80") (pin "2") (pinfunction "S_2") (pintype "passive"))
    )
    (net (code "480") (name "Net-(X80C-S)") (class "Default")
      (node (ref "Q48") (pin "C") (pinfunction "C_C") (pintype "passive"))
      (node (ref "X80") (pin "3") (pinfunction "S_3") (pintype "passive"))
    )
    (net (code "481") (name "unconnected-(Q1-C{slash}-Pad4)") (class "Default")
      (node (ref "Q1") (pin "4") (pinfunction "C/_4") (pintype "passive"))
    )
    (net (code "482") (name "unconnected-(Q4-C{slash}-Pad4)") (class "Default")
      (node (ref "Q4") (pin "4") (pinfunction "C/_4") (pintype "passive"))
    )
    (net (code "483") (name "unconnected-(Q7-C{slash}-Pad4)") (class "Default")
      (node (ref "Q7") (pin "4") (pinfunction "C/_4") (pintype "passive"))
    )
    (net (code "484") (name "unconnected-(Q10-C{slash}-Pad4)") (class "Default")
      (node (ref "Q10") (pin "4") (pinfunction "C/_4") (pintype "passive"))
    )
    (net (code "485") (name "unconnected-(Q13-C{slash}-Pad4)") (class "Default")
      (node (ref "Q13") (pin "4") (pinfunction "C/_4") (pintype "passive"))
    )
    (net (code "486") (name "unconnected-(Q16-C{slash}-Pad4)") (class "Default")
      (node (ref "Q16") (pin "4") (pinfunction "C/_4") (pintype "passive"))
    )
    (net (code "487") (name "unconnected-(Q19-C{slash}-Pad4)") (class "Default")
      (node (ref "Q19") (pin "4") (pinfunction "C/_4") (pintype "passive"))
    )
    (net (code "488") (name "unconnected-(Q22-C{slash}-Pad4)") (class "Default")
      (node (ref "Q22") (pin "4") (pinfunction "C/_4") (pintype "passive"))
    )
    (net (code "489") (name "unconnected-(Q25-C{slash}-Pad4)") (class "Default")
      (node (ref "Q25") (pin "4") (pinfunction "C/_4") (pintype "passive"))
    )
    (net (code "490") (name "unconnected-(Q28-C{slash}-Pad4)") (class "Default")
      (node (ref "Q28") (pin "4") (pinfunction "C/_4") (pintype "passive"))
    )
    (net (code "491") (name "unconnected-(Q31-C{slash}-Pad4)") (class "Default")
      (node (ref "Q31") (pin "4") (pinfunction "C/_4") (pintype "passive"))
    )
    (net (code "492") (name "unconnected-(Q34-C{slash}-Pad4)") (class "Default")
      (node (ref "Q34") (pin "4") (pinfunction "C/_4") (pintype "passive"))
    )
    (net (code "493") (name "unconnected-(Q37-C{slash}-Pad4)") (class "Default")
      (node (ref "Q37") (pin "4") (pinfunction "C/_4") (pintype "passive"))
    )
    (net (code "494") (name "unconnected-(Q40-C{slash}-Pad4)") (class "Default")
      (node (ref "Q40") (pin "4") (pinfunction "C/_4") (pintype "passive"))
    )
    (net (code "495") (name "unconnected-(Q43-C{slash}-Pad4)") (class "Default")
      (node (ref "Q43") (pin "4") (pinfunction "C/_4") (pintype "passive"))
    )
    (net (code "496") (name "unconnected-(Q46-C{slash}-Pad4)") (class "Default")
      (node (ref "Q46") (pin "4") (pinfunction "C/_4") (pintype "passive"))
    )
  )
)
